# pc_healthypi_5_3.net
KiCad netlist of a schematic drawn in EAGLE
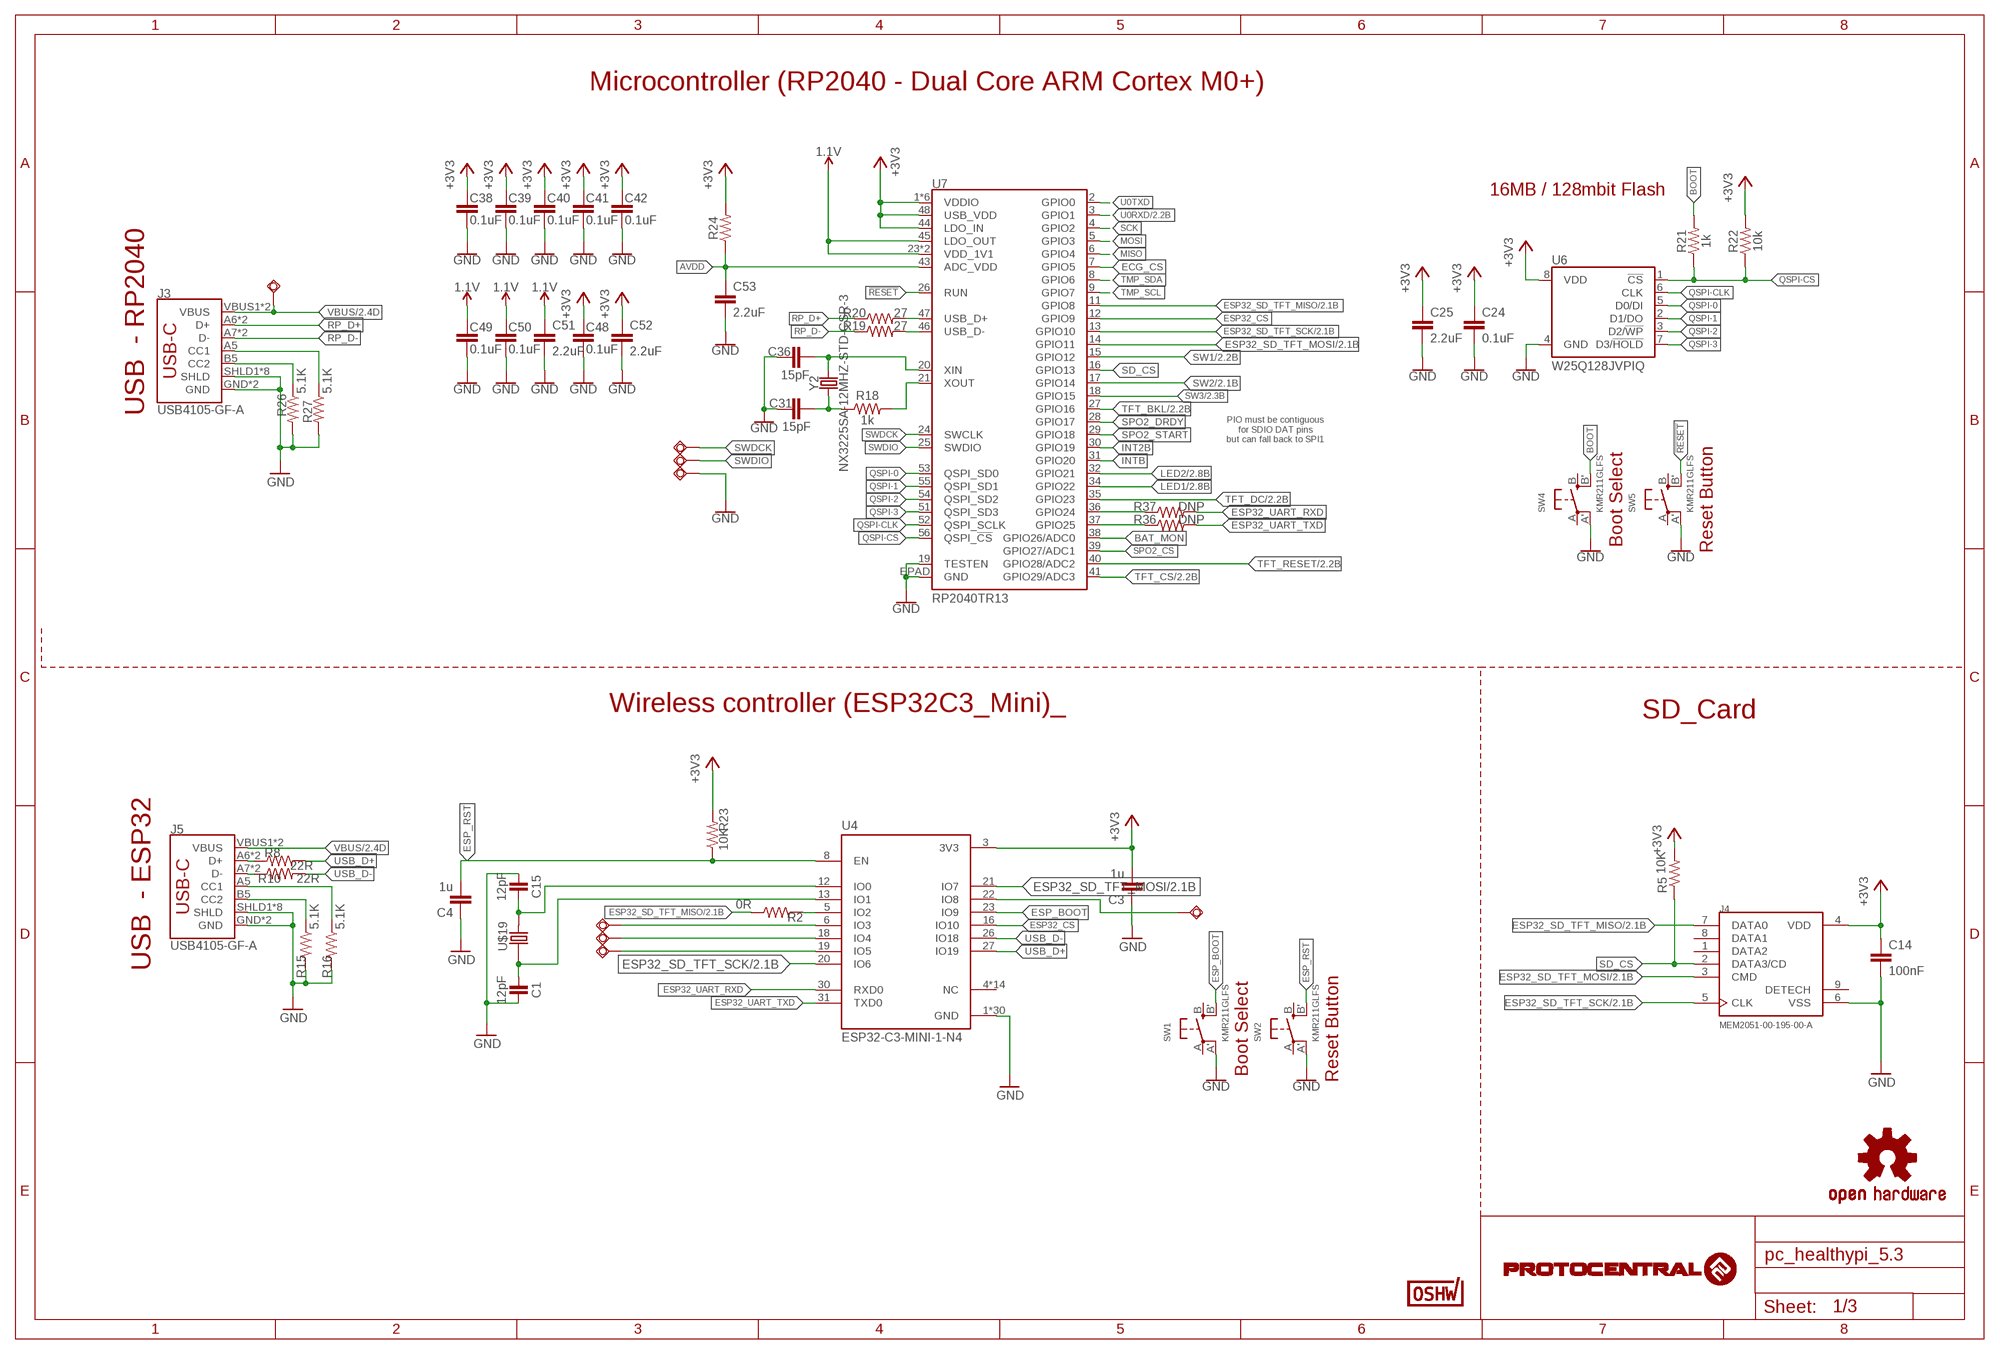
[diagram p0: schematic, sheet 1]
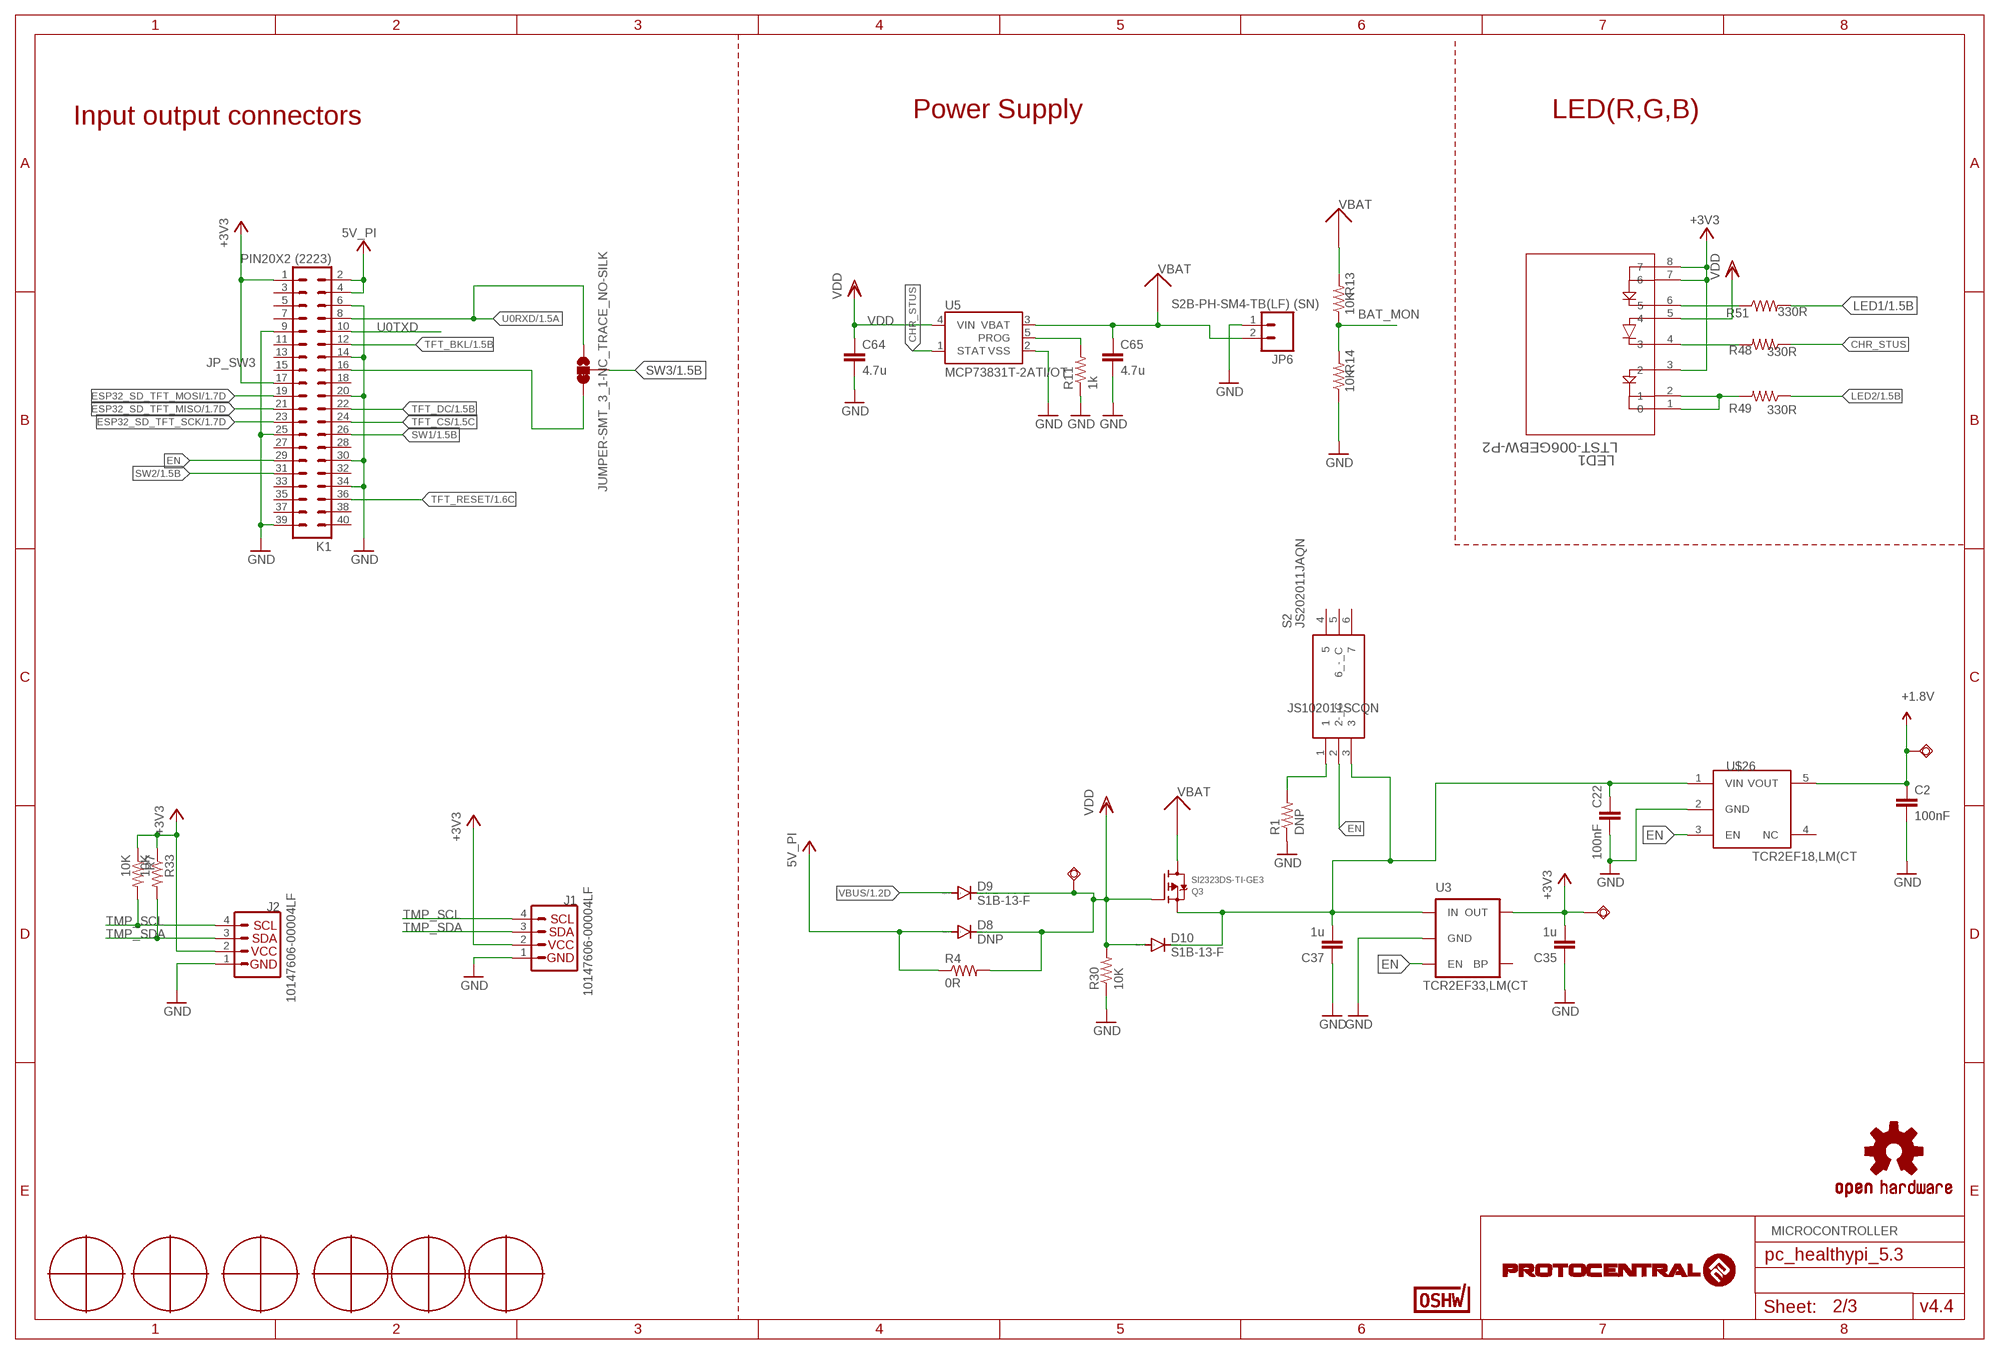
[diagram p1: schematic, sheet 2]
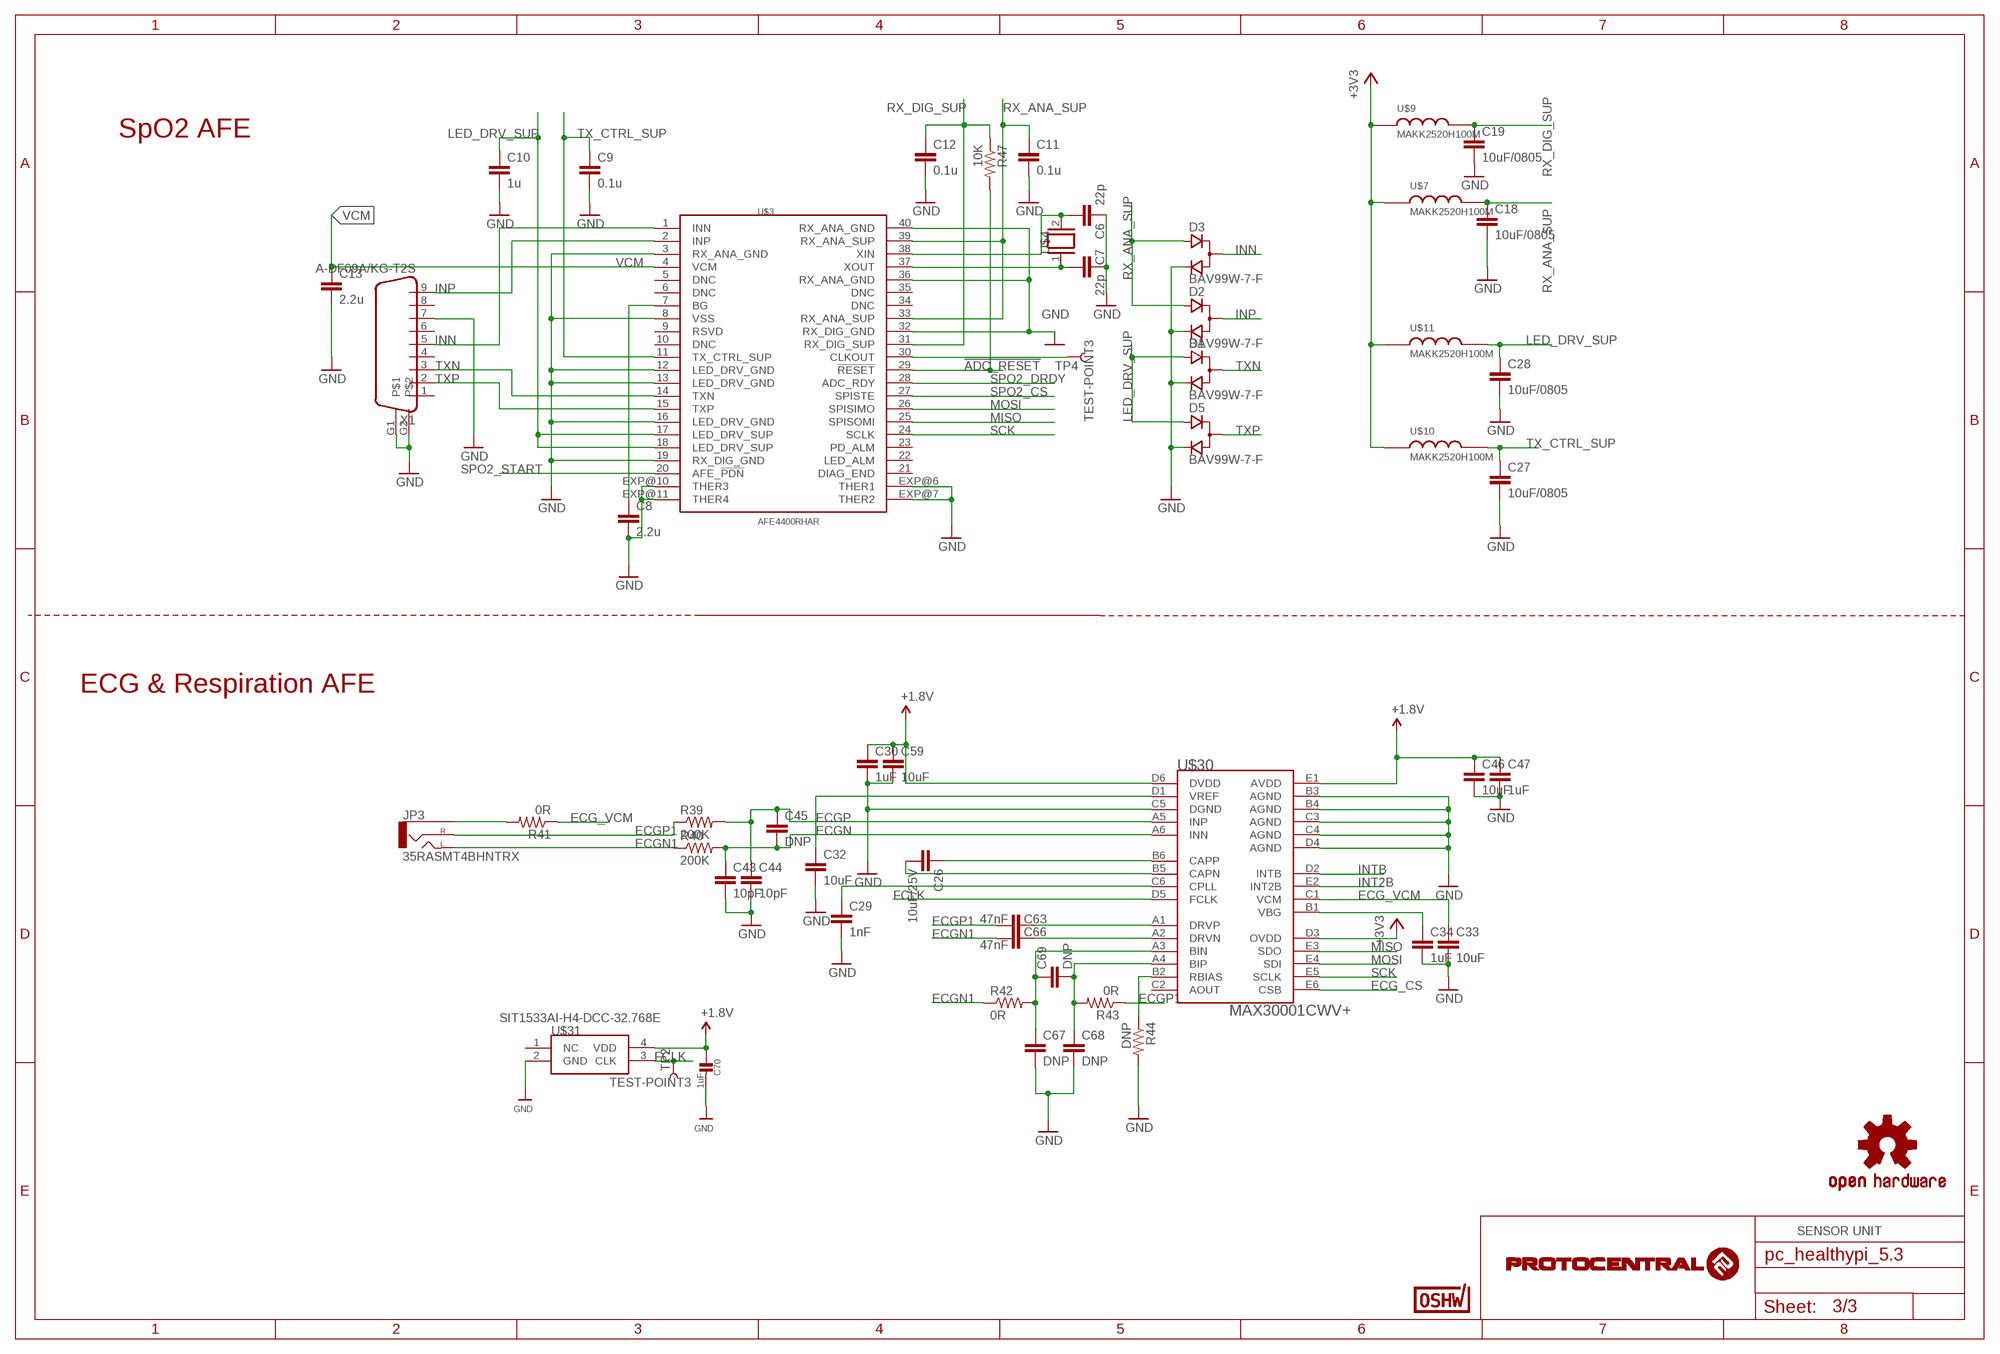
[diagram p2: schematic, sheet 3]

(export (version "E")
  (design (tool "Eeschema 10.0.6"))
  (components
    (comp (ref "C1")
      (value "12pF")
      (footprint "eagle-import:C0402")
      (libsource (lib "eagle-import") (part "CAPACITORS-0402"))
    )
    (comp (ref "C3")
      (value "1u")
      (footprint "eagle-import:C0402")
      (libsource (lib "eagle-import") (part "rcl_334_C-EUC0402"))
    )
    (comp (ref "C4")
      (value "1u")
      (footprint "eagle-import:C0402")
      (libsource (lib "eagle-import") (part "rcl_334_C-EUC0402"))
    )
    (comp (ref "C14")
      (value "100nF")
      (footprint "eagle-import:C0402")
      (libsource (lib "eagle-import") (part "C-EUC0402"))
    )
    (comp (ref "C15")
      (value "12pF")
      (footprint "eagle-import:C0402")
      (libsource (lib "eagle-import") (part "CAPACITORS-0402"))
    )
    (comp (ref "C24")
      (value "0.1uF")
      (footprint "eagle-import:0402-TIGHT")
      (libsource (lib "eagle-import") (part "0.1UF-0402T-6.3V-10%-X7R"))
    )
    (comp (ref "C25")
      (value "2.2uF")
      (footprint "eagle-import:0402-TIGHT")
      (libsource (lib "eagle-import") (part "2.2UF-0402_TIGHT-10V-10%-X5R"))
    )
    (comp (ref "C31")
      (value "15pF")
      (footprint "eagle-import:0402-TIGHT")
      (libsource (lib "eagle-import") (part "15PF-0402T-50V-5%"))
    )
    (comp (ref "C36")
      (value "15pF")
      (footprint "eagle-import:0402-TIGHT")
      (libsource (lib "eagle-import") (part "15PF-0402T-50V-5%"))
    )
    (comp (ref "C38")
      (value "0.1uF")
      (footprint "eagle-import:0402-TIGHT")
      (libsource (lib "eagle-import") (part "0.1UF-0402T-6.3V-10%-X7R"))
    )
    (comp (ref "C39")
      (value "0.1uF")
      (footprint "eagle-import:0402-TIGHT")
      (libsource (lib "eagle-import") (part "0.1UF-0402T-6.3V-10%-X7R"))
    )
    (comp (ref "C40")
      (value "0.1uF")
      (footprint "eagle-import:0402-TIGHT")
      (libsource (lib "eagle-import") (part "0.1UF-0402T-6.3V-10%-X7R"))
    )
    (comp (ref "C41")
      (value "0.1uF")
      (footprint "eagle-import:0402-TIGHT")
      (libsource (lib "eagle-import") (part "0.1UF-0402T-6.3V-10%-X7R"))
    )
    (comp (ref "C42")
      (value "0.1uF")
      (footprint "eagle-import:0402-TIGHT")
      (libsource (lib "eagle-import") (part "0.1UF-0402T-6.3V-10%-X7R"))
    )
    (comp (ref "C48")
      (value "0.1uF")
      (footprint "eagle-import:0402-TIGHT")
      (libsource (lib "eagle-import") (part "0.1UF-0402T-6.3V-10%-X7R"))
    )
    (comp (ref "C49")
      (value "0.1uF")
      (footprint "eagle-import:0402-TIGHT")
      (libsource (lib "eagle-import") (part "0.1UF-0402T-6.3V-10%-X7R"))
    )
    (comp (ref "C50")
      (value "0.1uF")
      (footprint "eagle-import:0402-TIGHT")
      (libsource (lib "eagle-import") (part "0.1UF-0402T-6.3V-10%-X7R"))
    )
    (comp (ref "C51")
      (value "2.2uF")
      (footprint "eagle-import:0402-TIGHT")
      (libsource (lib "eagle-import") (part "2.2UF-0402_TIGHT-10V-10%-X5R"))
    )
    (comp (ref "C52")
      (value "2.2uF")
      (footprint "eagle-import:0402-TIGHT")
      (libsource (lib "eagle-import") (part "2.2UF-0402_TIGHT-10V-10%-X5R"))
    )
    (comp (ref "C53")
      (value "2.2uF")
      (footprint "eagle-import:0402-TIGHT")
      (libsource (lib "eagle-import") (part "2.2UF-0402_TIGHT-10V-10%-X5R"))
    )
    (comp (ref "J3")
      (value "USB4105-GF-A")
      (footprint "eagle-import:USB-C-16P")
      (libsource (lib "eagle-import") (part "USB_C16PIN"))
    )
    (comp (ref "J4")
      (value "MEM2051-00-195-00-A")
      (footprint "eagle-import:GCT_MEM2051-00-195-00-A")
      (fields (field (name "MF") "Global Connector Technology"))
      (libsource (lib "eagle-import") (part "MEM2051-00-195-00-A"))
    )
    (comp (ref "J5")
      (value "USB4105-GF-A")
      (footprint "eagle-import:USB-C-16P")
      (libsource (lib "eagle-import") (part "circuitects_38825256_USB_C16PIN"))
    )
    (comp (ref "R2")
      (value "0R")
      (footprint "eagle-import:R0402")
      (libsource (lib "eagle-import") (part "rcl_334_R-US_R0402"))
    )
    (comp (ref "R5")
      (value "10K")
      (footprint "eagle-import:R0402")
      (libsource (lib "eagle-import") (part "R-US_R0402"))
    )
    (comp (ref "R8")
      (value "22R")
      (footprint "eagle-import:R0402")
      (libsource (lib "eagle-import") (part "rcl_334_R-US_R0402"))
    )
    (comp (ref "R10")
      (value "22R")
      (footprint "eagle-import:R0402")
      (libsource (lib "eagle-import") (part "rcl_334_R-US_R0402"))
    )
    (comp (ref "R15")
      (value "5.1K")
      (footprint "eagle-import:R0402")
      (libsource (lib "eagle-import") (part "rcl_334_R-US_R0402"))
    )
    (comp (ref "R16")
      (value "5.1K")
      (footprint "eagle-import:R0402")
      (libsource (lib "eagle-import") (part "rcl_334_R-US_R0402"))
    )
    (comp (ref "R18")
      (value "1k")
      (footprint "eagle-import:0402-TIGHT")
      (libsource (lib "eagle-import") (part "1KOHM-0402T-1/16W-1%"))
    )
    (comp (ref "R19")
      (value "27")
      (footprint "eagle-import:0402-TIGHT")
      (libsource (lib "eagle-import") (part "27OHM"))
    )
    (comp (ref "R20")
      (value "27")
      (footprint "eagle-import:0402-TIGHT")
      (libsource (lib "eagle-import") (part "27OHM"))
    )
    (comp (ref "R21")
      (value "1k")
      (footprint "eagle-import:0402-TIGHT")
      (libsource (lib "eagle-import") (part "1KOHM-0402T-1/16W-1%"))
    )
    (comp (ref "R22")
      (value "10k")
      (footprint "eagle-import:0402-TIGHT")
      (libsource (lib "eagle-import") (part "10KOHM-0402T-1/16W-1%"))
    )
    (comp (ref "R23")
      (value "10K")
      (footprint "eagle-import:R0402")
      (libsource (lib "eagle-import") (part "rcl_334_R-US_R0402"))
    )
    (comp (ref "R24")
      (value "200OHM-0402T-1/16W-1%")
      (footprint "eagle-import:0402-TIGHT")
      (libsource (lib "eagle-import") (part "200OHM-0402T-1/16W-1%"))
    )
    (comp (ref "R26")
      (value "5.1K")
      (footprint "eagle-import:R0402")
      (libsource (lib "eagle-import") (part "rcl_334_R-US_R0402"))
    )
    (comp (ref "R27")
      (value "5.1K")
      (footprint "eagle-import:R0402")
      (libsource (lib "eagle-import") (part "rcl_334_R-US_R0402"))
    )
    (comp (ref "R36")
      (value "DNP")
      (footprint "eagle-import:0402-TIGHT")
      (libsource (lib "eagle-import") (part "27OHM"))
    )
    (comp (ref "R37")
      (value "DNP")
      (footprint "eagle-import:0402-TIGHT")
      (libsource (lib "eagle-import") (part "27OHM"))
    )
    (comp (ref "SW1")
      (value "KMR211GLFS")
      (footprint "eagle-import:BTN_KMR2_4.6X2.8")
      (libsource (lib "eagle-import") (part "SWITCH_TACT_SMT4.6X2.8"))
    )
    (comp (ref "SW2")
      (value "KMR211GLFS")
      (footprint "eagle-import:BTN_KMR2_4.6X2.8")
      (libsource (lib "eagle-import") (part "SWITCH_TACT_SMT4.6X2.8"))
    )
    (comp (ref "SW4")
      (value "KMR211GLFS")
      (footprint "eagle-import:BTN_KMR2_4.6X2.8")
      (libsource (lib "eagle-import") (part "SWITCH_TACT_SMT4.6X2.8"))
    )
    (comp (ref "SW5")
      (value "KMR211GLFS")
      (footprint "eagle-import:BTN_KMR2_4.6X2.8")
      (libsource (lib "eagle-import") (part "SWITCH_TACT_SMT4.6X2.8"))
    )
    (comp (ref "SWIO2")
      (value "TPSQTP11R")
      (footprint "eagle-import:TP11R")
      (libsource (lib "eagle-import") (part "TPSQTP11R"))
    )
    (comp (ref "SWIO3")
      (value "TPSQTP11R")
      (footprint "eagle-import:TP11R")
      (libsource (lib "eagle-import") (part "TPSQTP11R"))
    )
    (comp (ref "SWIO4")
      (value "TPSQTP11R")
      (footprint "eagle-import:TP11R")
      (libsource (lib "eagle-import") (part "TPSQTP11R"))
    )
    (comp (ref "SWIO6")
      (value "TPSQTP11R")
      (footprint "eagle-import:TP11R")
      (libsource (lib "eagle-import") (part "TPSQTP11R"))
    )
    (comp (ref "TP1")
      (value "TPSQTP11R")
      (footprint "eagle-import:TP11R")
      (libsource (lib "eagle-import") (part "TPSQTP11R"))
    )
    (comp (ref "TP5")
      (value "TPSQTP11R")
      (footprint "eagle-import:TP11R")
      (libsource (lib "eagle-import") (part "TPSQTP11R"))
    )
    (comp (ref "TP6")
      (value "TPSQTP11R")
      (footprint "eagle-import:TP11R")
      (libsource (lib "eagle-import") (part "TPSQTP11R"))
    )
    (comp (ref "TP7")
      (value "TPSQTP11R")
      (footprint "eagle-import:TP11R")
      (libsource (lib "eagle-import") (part "TPSQTP11R"))
    )
    (comp (ref "U$19")
      (value "520-327-12.5-34B(32.768KHZ)")
      (footprint "eagle-import:ECX-31B")
      (libsource (lib "eagle-import") (part "ECS-X-34B"))
    )
    (comp (ref "U$35")
      (value "OSHW-LOGOM")
      (footprint "eagle-import:OSHW-LOGO-M")
      (libsource (lib "eagle-import") (part "OSHW-LOGOM"))
    )
    (comp (ref "U$37")
      (value "CERT-SMALL")
      (footprint "eagle-import:CERT-SMALL-SILK")
      (libsource (lib "eagle-import") (part "CERT-SMALL"))
    )
    (comp (ref "U4")
      (value "ESP32-C3-MINI-1-N4")
      (footprint "eagle-import:XCVR_ESP32-C3-MINI-1-N4")
      (fields (field (name "MF") "Espressif Systems"))
      (libsource (lib "eagle-import") (part "ESP32-C3-MINI-1-N4"))
    )
    (comp (ref "U6")
      (value "W25Q128JVPIQ")
      (footprint "eagle-import:WSON-8-6X5-SKINNY_CENTERPAD")
      (libsource (lib "eagle-import") (part "W25QXX128MBIT-6X5-SKINNY_CENTER"))
    )
    (comp (ref "U7")
      (value "RP2040TR13")
      (footprint "eagle-import:QFN-56")
      (libsource (lib "eagle-import") (part "RP2040"))
    )
    (comp (ref "Y2")
      (value "NX3225SA-12MHZ-STD-CSR-3")
      (footprint "eagle-import:CRYSTAL-SMD-2X2.5MM")
      (libsource (lib "eagle-import") (part "CRYSTAL-12MHZ"))
    )
    (comp (ref "C6")
      (value "22p")
      (footprint "eagle-import:C0402")
      (libsource (lib "eagle-import") (part "rcl_334_C-EUC0402"))
    )
    (comp (ref "C7")
      (value "22p")
      (footprint "eagle-import:C0402")
      (libsource (lib "eagle-import") (part "rcl_334_C-EUC0402"))
    )
    (comp (ref "C8")
      (value "2.2u")
      (footprint "eagle-import:C0402")
      (libsource (lib "eagle-import") (part "rcl_334_C-EUC0402"))
    )
    (comp (ref "C9")
      (value "0.1u")
      (footprint "eagle-import:C0402")
      (libsource (lib "eagle-import") (part "rcl_334_C-EUC0402"))
    )
    (comp (ref "C10")
      (value "1u")
      (footprint "eagle-import:C0805")
      (libsource (lib "eagle-import") (part "rcl_334_C-EUC0805"))
    )
    (comp (ref "C11")
      (value "0.1u")
      (footprint "eagle-import:C0402")
      (libsource (lib "eagle-import") (part "rcl_334_C-EUC0402"))
    )
    (comp (ref "C12")
      (value "0.1u")
      (footprint "eagle-import:C0402")
      (libsource (lib "eagle-import") (part "rcl_334_C-EUC0402"))
    )
    (comp (ref "C13")
      (value "2.2u")
      (footprint "eagle-import:C0402")
      (libsource (lib "eagle-import") (part "rcl_334_C-EUC0402"))
    )
    (comp (ref "C18")
      (value "10uF/0805")
      (footprint "eagle-import:C0805")
      (libsource (lib "eagle-import") (part "rcl_334_C-EUC0805"))
    )
    (comp (ref "C19")
      (value "10uF/0805")
      (footprint "eagle-import:C0805")
      (libsource (lib "eagle-import") (part "rcl_334_C-EUC0805"))
    )
    (comp (ref "C26")
      (value "10uF/25V")
      (footprint "eagle-import:C0805")
      (libsource (lib "eagle-import") (part "rcl_334_C-EUC0805"))
    )
    (comp (ref "C27")
      (value "10uF/0805")
      (footprint "eagle-import:C0805")
      (libsource (lib "eagle-import") (part "rcl_334_C-EUC0805"))
    )
    (comp (ref "C28")
      (value "10uF/0805")
      (footprint "eagle-import:C0805")
      (libsource (lib "eagle-import") (part "rcl_334_C-EUC0805"))
    )
    (comp (ref "C29")
      (value "1nF")
      (footprint "eagle-import:C0402")
      (libsource (lib "eagle-import") (part "rcl_334_C-EUC0402"))
    )
    (comp (ref "C30")
      (value "1uF")
      (footprint "eagle-import:C0402")
      (libsource (lib "eagle-import") (part "rcl_334_C-EUC0402"))
    )
    (comp (ref "C32")
      (value "10uF")
      (footprint "eagle-import:C0805")
      (libsource (lib "eagle-import") (part "rcl_334_C-EUC0805"))
    )
    (comp (ref "C33")
      (value "10uF")
      (footprint "eagle-import:C0805")
      (libsource (lib "eagle-import") (part "rcl_334_C-EUC0805"))
    )
    (comp (ref "C34")
      (value "1uF")
      (footprint "eagle-import:C0402")
      (libsource (lib "eagle-import") (part "rcl_334_C-EUC0402"))
    )
    (comp (ref "C43")
      (value "10pF")
      (footprint "eagle-import:C0402")
      (libsource (lib "eagle-import") (part "rcl_334_C-EUC0402"))
    )
    (comp (ref "C44")
      (value "10pF")
      (footprint "eagle-import:C0402")
      (libsource (lib "eagle-import") (part "rcl_334_C-EUC0402"))
    )
    (comp (ref "C45")
      (value "DNP")
      (footprint "eagle-import:C0402")
      (libsource (lib "eagle-import") (part "rcl_334_C-EUC0402"))
    )
    (comp (ref "C46")
      (value "10uF")
      (footprint "eagle-import:C0805")
      (libsource (lib "eagle-import") (part "rcl_334_C-EUC0805"))
    )
    (comp (ref "C47")
      (value "1uF")
      (footprint "eagle-import:C0402")
      (libsource (lib "eagle-import") (part "rcl_334_C-EUC0402"))
    )
    (comp (ref "C59")
      (value "10uF")
      (footprint "eagle-import:C0805")
      (libsource (lib "eagle-import") (part "rcl_334_C-EUC0805"))
    )
    (comp (ref "C63")
      (value "47nF")
      (footprint "eagle-import:C0402")
      (libsource (lib "eagle-import") (part "rcl_334_C-EUC0402"))
    )
    (comp (ref "C66")
      (value "47nF")
      (footprint "eagle-import:C0402")
      (libsource (lib "eagle-import") (part "rcl_334_C-EUC0402"))
    )
    (comp (ref "C67")
      (value "DNP")
      (footprint "eagle-import:C0402")
      (libsource (lib "eagle-import") (part "rcl_334_C-EUC0402"))
    )
    (comp (ref "C68")
      (value "DNP")
      (footprint "eagle-import:C0402")
      (libsource (lib "eagle-import") (part "rcl_334_C-EUC0402"))
    )
    (comp (ref "C69")
      (value "DNP")
      (footprint "eagle-import:C0402")
      (libsource (lib "eagle-import") (part "rcl_334_C-EUC0402"))
    )
    (comp (ref "C70")
      (value "1uF")
      (footprint "eagle-import:0402")
      (libsource (lib "eagle-import") (part "CAP_CERAMIC0402"))
    )
    (comp (ref "D1")
      (value "BAV99W-7-F")
      (footprint "eagle-import:SOT323")
      (libsource (lib "eagle-import") (part "D_ACACSOT323"))
    )
    (comp (ref "D2")
      (value "BAV99W-7-F")
      (footprint "eagle-import:SOT323")
      (libsource (lib "eagle-import") (part "D_ACACSOT323"))
    )
    (comp (ref "D3")
      (value "BAV99W-7-F")
      (footprint "eagle-import:SOT323")
      (libsource (lib "eagle-import") (part "D_ACACSOT323"))
    )
    (comp (ref "D5")
      (value "BAV99W-7-F")
      (footprint "eagle-import:SOT323")
      (libsource (lib "eagle-import") (part "D_ACACSOT323"))
    )
    (comp (ref "JP3")
      (value "35RASMT4BHNTRX")
      (footprint "eagle-import:AUDIO-JACK-3.5MM-SMD")
      (libsource (lib "eagle-import") (part "AUDIO-JACKSMD2"))
    )
    (comp (ref "R39")
      (value "200K")
      (footprint "eagle-import:0805")
      (libsource (lib "eagle-import") (part "RESISTOR0805-RES"))
    )
    (comp (ref "R40")
      (value "200K")
      (footprint "eagle-import:0805")
      (libsource (lib "eagle-import") (part "RESISTOR0805-RES"))
    )
    (comp (ref "R41")
      (value "0R")
      (footprint "eagle-import:0805")
      (libsource (lib "eagle-import") (part "RESISTOR0805-RES"))
    )
    (comp (ref "R42")
      (value "0R")
      (footprint "eagle-import:0402-RES")
      (libsource (lib "eagle-import") (part "RESISTOR0402-RES"))
    )
    (comp (ref "R43")
      (value "0R")
      (footprint "eagle-import:0402-RES")
      (libsource (lib "eagle-import") (part "RESISTOR0402-RES"))
    )
    (comp (ref "R44")
      (value "DNP")
      (footprint "eagle-import:0402-RES")
      (libsource (lib "eagle-import") (part "RESISTOR0402-RES"))
    )
    (comp (ref "R47")
      (value "10K")
      (footprint "eagle-import:R0402")
      (libsource (lib "eagle-import") (part "rcl_334_R-US_R0402"))
    )
    (comp (ref "TP2")
      (value "TEST-POINT3")
      (footprint "eagle-import:PAD.03X.03")
      (libsource (lib "eagle-import") (part "TEST-POINT3"))
    )
    (comp (ref "TP4")
      (value "TEST-POINT3")
      (footprint "eagle-import:PAD.03X.03")
      (libsource (lib "eagle-import") (part "TEST-POINT3"))
    )
    (comp (ref "U$3")
      (value "AFE4400RHAR")
      (footprint "eagle-import:QFN-40")
      (libsource (lib "eagle-import") (part "AFE4400"))
    )
    (comp (ref "U$4")
      (value "ABM3-8.000MHZ-B4Y-T")
      (footprint "eagle-import:XTAL_HC49P488W43L1150T466H350")
      (fields (field (name "MF") "Citizen Finedevice Co Ltd") (field (name "MP") "HC-49/U-S16000000ABJB"))
      (libsource (lib "eagle-import") (part "HC-49/U-S16000000ABJB"))
    )
    (comp (ref "U$7")
      (value "MAKK2520H100M")
      (footprint "eagle-import:LPS")
      (libsource (lib "eagle-import") (part "LPS"))
    )
    (comp (ref "U$9")
      (value "MAKK2520H100M")
      (footprint "eagle-import:LPS")
      (libsource (lib "eagle-import") (part "LPS"))
    )
    (comp (ref "U$10")
      (value "MAKK2520H100M")
      (footprint "eagle-import:LPS")
      (libsource (lib "eagle-import") (part "LPS"))
    )
    (comp (ref "U$11")
      (value "MAKK2520H100M")
      (footprint "eagle-import:LPS")
      (libsource (lib "eagle-import") (part "LPS"))
    )
    (comp (ref "U$24")
      (value "OSHW-LOGOM")
      (footprint "eagle-import:OSHW-LOGO-M")
      (libsource (lib "eagle-import") (part "OSHW-LOGOM"))
    )
    (comp (ref "U$30")
      (value "MAX30001CWV+")
      (footprint "eagle-import:30WLP")
      (libsource (lib "eagle-import") (part "MAX30001CWV+"))
    )
    (comp (ref "U$31")
      (value "SIT1533AI-H4-DCC-32.768E")
      (footprint "eagle-import:SIT1533")
      (libsource (lib "eagle-import") (part "SIT1533"))
    )
    (comp (ref "U$36")
      (value "CERT-SMALL")
      (footprint "eagle-import:CERT-SMALL-SILK")
      (libsource (lib "eagle-import") (part "CERT-SMALL"))
    )
    (comp (ref "X1")
      (value "A-DF09A/KG-T2S")
      (footprint "eagle-import:DB9")
      (libsource (lib "eagle-import") (part "DB9"))
    )
    (comp (ref "C2")
      (value "100nF")
      (footprint "eagle-import:C0402")
      (libsource (lib "eagle-import") (part "rcl_334_C-EUC0402"))
    )
    (comp (ref "C22")
      (value "100nF")
      (footprint "eagle-import:C0402")
      (libsource (lib "eagle-import") (part "rcl_334_C-EUC0402"))
    )
    (comp (ref "C35")
      (value "1u")
      (footprint "eagle-import:C0402")
      (libsource (lib "eagle-import") (part "rcl_334_C-EUC0402"))
    )
    (comp (ref "C37")
      (value "1u")
      (footprint "eagle-import:C0402")
      (libsource (lib "eagle-import") (part "rcl_334_C-EUC0402"))
    )
    (comp (ref "C64")
      (value "4.7u")
      (footprint "eagle-import:C0805")
      (libsource (lib "eagle-import") (part "rcl_334_C-EUC0805"))
    )
    (comp (ref "C65")
      (value "4.7u")
      (footprint "eagle-import:C0805")
      (libsource (lib "eagle-import") (part "rcl_334_C-EUC0805"))
    )
    (comp (ref "D8")
      (value "DNP")
      (footprint "eagle-import:SOD-123_MINI-SMA")
      (libsource (lib "eagle-import") (part "CGRM400-G1"))
    )
    (comp (ref "D9")
      (value "S1B-13-F")
      (footprint "eagle-import:SOD-123_MINI-SMA")
      (libsource (lib "eagle-import") (part "CGRM400-G1"))
    )
    (comp (ref "D10")
      (value "S1B-13-F")
      (footprint "eagle-import:SOD-123_MINI-SMA")
      (libsource (lib "eagle-import") (part "CGRM400-G1"))
    )
    (comp (ref "J1")
      (value "10147606-00004LF")
      (footprint "eagle-import:JST04_1MM_RA")
      (libsource (lib "eagle-import") (part "QWIIC_CONNECTORJS-1MM"))
    )
    (comp (ref "J2")
      (value "10147606-00004LF")
      (footprint "eagle-import:JST04_1MM_RA")
      (libsource (lib "eagle-import") (part "QWIIC_CONNECTORJS-1MM"))
    )
    (comp (ref "JP6")
      (value "S2B-PH-SM4-TB(LF) (SN)")
      (footprint "eagle-import:JST-2-SMD")
      (libsource (lib "eagle-import") (part "M02-JST-2MM-SMT"))
    )
    (comp (ref "JP_SW3")
      (value "JUMPER-SMT_3_1-NC_TRACE_NO-SILK")
      (footprint "eagle-import:SMT-JUMPER_3_1-NC_TRACE_NO-SILK")
      (libsource (lib "eagle-import") (part "JUMPER-SMT_3_1-NC_TRACE_NO-SILK"))
    )
    (comp (ref "K1")
      (value "PIN20X2 (2223)")
      (footprint "eagle-import:PIN_20X2")
      (libsource (lib "eagle-import") (part "PIN20X2"))
    )
    (comp (ref "LED1")
      (value "LTST-006GEBW-P2")
      (footprint "eagle-import:LTST-008BGEW_LTO")
      (fields (field (name "COPYRIGHT") "Copyright (C) 2023 Ultra Librarian. All rights reserved."))
      (libsource (lib "eagle-import") (part "LTST-006GEBW-P2"))
    )
    (comp (ref "Q3")
      (value "SI2323DS-TI-GE3")
      (footprint "eagle-import:SOT23-R")
      (libsource (lib "eagle-import") (part "MOSFET-P"))
    )
    (comp (ref "R1")
      (value "DNP")
      (footprint "eagle-import:R0402")
      (libsource (lib "eagle-import") (part "rcl_334_R-US_R0402"))
    )
    (comp (ref "R4")
      (value "0R")
      (footprint "eagle-import:0805")
      (libsource (lib "eagle-import") (part "RESISTOR0805-RES"))
    )
    (comp (ref "R7")
      (value "10K")
      (footprint "eagle-import:R0402")
      (libsource (lib "eagle-import") (part "rcl_334_R-US_R0402"))
    )
    (comp (ref "R11")
      (value "1k")
      (footprint "eagle-import:R0402")
      (libsource (lib "eagle-import") (part "rcl_334_R-US_R0402"))
    )
    (comp (ref "R13")
      (value "10K")
      (footprint "eagle-import:R0402")
      (libsource (lib "eagle-import") (part "rcl_334_R-US_R0402"))
    )
    (comp (ref "R14")
      (value "10K")
      (footprint "eagle-import:R0402")
      (libsource (lib "eagle-import") (part "rcl_334_R-US_R0402"))
    )
    (comp (ref "R30")
      (value "10K")
      (footprint "eagle-import:R0402")
      (libsource (lib "eagle-import") (part "rcl_334_R-US_R0402"))
    )
    (comp (ref "R33")
      (value "10K")
      (footprint "eagle-import:R0402")
      (libsource (lib "eagle-import") (part "rcl_334_R-US_R0402"))
    )
    (comp (ref "R48")
      (value "330R")
      (footprint "eagle-import:0402-RES")
      (libsource (lib "eagle-import") (part "RESISTOR0402-RES"))
    )
    (comp (ref "R49")
      (value "330R")
      (footprint "eagle-import:0402-RES")
      (libsource (lib "eagle-import") (part "RESISTOR0402-RES"))
    )
    (comp (ref "R51")
      (value "330R")
      (footprint "eagle-import:0402-RES")
      (libsource (lib "eagle-import") (part "RESISTOR0402-RES"))
    )
    (comp (ref "S2")
      (value "JS202011JAQN")
      (footprint "eagle-import:JS202011JAQN")
      (fields (field (name "MF") "C&K"))
      (libsource (lib "eagle-import") (part "JS202011JAQN"))
    )
    (comp (ref "SWIO1")
      (value "TPSQTP11R")
      (footprint "eagle-import:TP11R")
      (libsource (lib "eagle-import") (part "TPSQTP11R"))
    )
    (comp (ref "SWIO5")
      (value "TPSQTP11R")
      (footprint "eagle-import:TP11R")
      (libsource (lib "eagle-import") (part "TPSQTP11R"))
    )
    (comp (ref "SWIO7")
      (value "TPSQTP11R")
      (footprint "eagle-import:TP11R")
      (libsource (lib "eagle-import") (part "TPSQTP11R"))
    )
    (comp (ref "U$1")
      (value "FUDCIALPOINTS")
      (footprint "eagle-import:FIDUCIALPOINTS")
      (libsource (lib "eagle-import") (part "circuitects_38825256_FUDCIALPOINTS"))
    )
    (comp (ref "U$5")
      (value "OSHW-LOGOM")
      (footprint "eagle-import:OSHW-LOGO-M")
      (libsource (lib "eagle-import") (part "OSHW-LOGOM"))
    )
    (comp (ref "U$13")
      (value "CERT-SMALL")
      (footprint "eagle-import:CERT-SMALL-SILK")
      (libsource (lib "eagle-import") (part "CERT-SMALL"))
    )
    (comp (ref "U$21")
      (value "FUDCIALPOINTS")
      (footprint "eagle-import:FIDUCIALPOINTS")
      (libsource (lib "eagle-import") (part "FUDCIALPOINTS"))
    )
    (comp (ref "U$23")
      (value "FUDCIALPOINTS")
      (footprint "eagle-import:FIDUCIALPOINTS")
      (libsource (lib "eagle-import") (part "circuitects_38825256_FUDCIALPOINTS"))
    )
    (comp (ref "U$25")
      (value "FUDCIALPOINTS")
      (footprint "eagle-import:FIDUCIALPOINTS")
      (libsource (lib "eagle-import") (part "circuitects_38825256_FUDCIALPOINTS"))
    )
    (comp (ref "U$26")
      (value "TCR2EF18,LM(CT")
      (footprint "eagle-import:SOT95P285X140-5N")
      (libsource (lib "eagle-import") (part "AP7354D-18W5-7"))
    )
    (comp (ref "U$28")
      (value "FUDCIALPOINTS")
      (footprint "eagle-import:FIDUCIALPOINTS")
      (libsource (lib "eagle-import") (part "FUDCIALPOINTS"))
    )
    (comp (ref "U$29")
      (value "FUDCIALPOINTS")
      (footprint "eagle-import:FIDUCIALPOINTS")
      (libsource (lib "eagle-import") (part "FUDCIALPOINTS"))
    )
    (comp (ref "U3")
      (value "TCR2EF33,LM(CT")
      (footprint "eagle-import:SOT23-5")
      (libsource (lib "eagle-import") (part "V_REG_LDOSMD"))
    )
    (comp (ref "U5")
      (value "MCP73831T-2ATI/OT")
      (footprint "eagle-import:SOT23-5")
      (libsource (lib "eagle-import") (part "MCP73831"))
    )
  )
  (nets
    (net (code "1") (name "+1.8V") (class "Default")
      (node (ref "C2") (pin "1") (pinfunction "1_1") (pintype "passive"))
      (node (ref "C30") (pin "1") (pinfunction "1_1") (pintype "passive"))
      (node (ref "C46") (pin "1") (pinfunction "1_1") (pintype "passive"))
      (node (ref "C47") (pin "1") (pinfunction "1_1") (pintype "passive"))
      (node (ref "C59") (pin "1") (pinfunction "1_1") (pintype "passive"))
      (node (ref "C70") (pin "1") (pinfunction "P$1_1") (pintype "passive"))
      (node (ref "SWIO5") (pin "TP") (pinfunction "TP_TP") (pintype "input"))
      (node (ref "U$26") (pin "5") (pinfunction "VOUT_5") (pintype "bidirectional"))
      (node (ref "U$30") (pin "D6") (pinfunction "DVDD_D6") (pintype "bidirectional"))
      (node (ref "U$30") (pin "E1") (pinfunction "AVDD_E1") (pintype "bidirectional"))
      (node (ref "U$31") (pin "4") (pinfunction "VDD_4") (pintype "bidirectional"))
    )
    (net (code "2") (name "+3V3") (class "Default")
      (node (ref "C14") (pin "1") (pinfunction "1_1") (pintype "passive"))
      (node (ref "C24") (pin "1") (pinfunction "1_1") (pintype "passive"))
      (node (ref "C25") (pin "1") (pinfunction "1_1") (pintype "passive"))
      (node (ref "C3") (pin "2") (pinfunction "2_2") (pintype "passive"))
      (node (ref "C35") (pin "2") (pinfunction "2_2") (pintype "passive"))
      (node (ref "C38") (pin "1") (pinfunction "1_1") (pintype "passive"))
      (node (ref "C39") (pin "1") (pinfunction "1_1") (pintype "passive"))
      (node (ref "C40") (pin "1") (pinfunction "1_1") (pintype "passive"))
      (node (ref "C41") (pin "1") (pinfunction "1_1") (pintype "passive"))
      (node (ref "C42") (pin "1") (pinfunction "1_1") (pintype "passive"))
      (node (ref "C48") (pin "1") (pinfunction "1_1") (pintype "passive"))
      (node (ref "C52") (pin "1") (pinfunction "1_1") (pintype "passive"))
      (node (ref "J1") (pin "2") (pinfunction "2_2") (pintype "power_in"))
      (node (ref "J2") (pin "2") (pinfunction "2_2") (pintype "power_in"))
      (node (ref "J4") (pin "4") (pinfunction "VDD_4") (pintype "power_in"))
      (node (ref "K1") (pin "1") (pinfunction "1_1") (pintype "passive"))
      (node (ref "K1") (pin "17") (pinfunction "17_17") (pintype "passive"))
      (node (ref "LED1") (pin "3") (pinfunction "2_3") (pintype "passive"))
      (node (ref "LED1") (pin "7") (pinfunction "6_7") (pintype "passive"))
      (node (ref "LED1") (pin "8") (pinfunction "7_8") (pintype "passive"))
      (node (ref "R22") (pin "2") (pinfunction "2_2") (pintype "passive"))
      (node (ref "R23") (pin "2") (pinfunction "2_2") (pintype "passive"))
      (node (ref "R24") (pin "2") (pinfunction "2_2") (pintype "passive"))
      (node (ref "R33") (pin "1") (pinfunction "1_1") (pintype "passive"))
      (node (ref "R5") (pin "2") (pinfunction "2_2") (pintype "passive"))
      (node (ref "R7") (pin "1") (pinfunction "1_1") (pintype "passive"))
      (node (ref "SWIO1") (pin "TP") (pinfunction "TP_TP") (pintype "input"))
      (node (ref "U$10") (pin "1") (pinfunction "P$1_1") (pintype "bidirectional"))
      (node (ref "U$11") (pin "1") (pinfunction "P$1_1") (pintype "bidirectional"))
      (node (ref "U$30") (pin "D3") (pinfunction "OVDD_D3") (pintype "bidirectional"))
      (node (ref "U$7") (pin "1") (pinfunction "P$1_1") (pintype "bidirectional"))
      (node (ref "U$9") (pin "1") (pinfunction "P$1_1") (pintype "bidirectional"))
      (node (ref "U3") (pin "5") (pinfunction "OUT_5") (pintype "passive"))
      (node (ref "U4") (pin "3") (pinfunction "3V3_3") (pintype "power_in"))
      (node (ref "U6") (pin "8") (pinfunction "VDD_8") (pintype "bidirectional"))
      (node (ref "U7") (pin "1") (pinfunction "VDDIO_1") (pintype "bidirectional"))
      (node (ref "U7") (pin "10") (pinfunction "VDDIO_10") (pintype "bidirectional"))
      (node (ref "U7") (pin "22") (pinfunction "VDDIO_22") (pintype "bidirectional"))
      (node (ref "U7") (pin "33") (pinfunction "VDDIO_33") (pintype "bidirectional"))
      (node (ref "U7") (pin "42") (pinfunction "VDDIO_42") (pintype "bidirectional"))
      (node (ref "U7") (pin "44") (pinfunction "LDO_IN_44") (pintype "bidirectional"))
      (node (ref "U7") (pin "48") (pinfunction "USB_VDD_48") (pintype "bidirectional"))
      (node (ref "U7") (pin "49") (pinfunction "VDDIO_49") (pintype "bidirectional"))
    )
    (net (code "3") (name "+5V") (class "Default")
      (node (ref "D8") (pin "A") (pinfunction "A_A") (pintype "passive"))
      (node (ref "K1") (pin "2") (pinfunction "2_2") (pintype "passive"))
      (node (ref "K1") (pin "4") (pinfunction "4_4") (pintype "passive"))
      (node (ref "R4") (pin "1") (pinfunction "1_1") (pintype "passive"))
    )
    (net (code "4") (name "1.1V") (class "Default")
      (node (ref "C49") (pin "1") (pinfunction "1_1") (pintype "passive"))
      (node (ref "C50") (pin "1") (pinfunction "1_1") (pintype "passive"))
      (node (ref "C51") (pin "1") (pinfunction "1_1") (pintype "passive"))
      (node (ref "U7") (pin "23") (pinfunction "VDD_1V1_23") (pintype "bidirectional"))
      (node (ref "U7") (pin "45") (pinfunction "LDO_OUT_45") (pintype "bidirectional"))
      (node (ref "U7") (pin "50") (pinfunction "VDD_1V1_50") (pintype "bidirectional"))
    )
    (net (code "5") (name "AVDD") (class "Default")
      (node (ref "C53") (pin "1") (pinfunction "1_1") (pintype "passive"))
      (node (ref "R24") (pin "1") (pinfunction "1_1") (pintype "passive"))
      (node (ref "U7") (pin "43") (pinfunction "ADC_VDD_43") (pintype "bidirectional"))
    )
    (net (code "6") (name "BAT_MON") (class "Default")
      (node (ref "R13") (pin "1") (pinfunction "1_1") (pintype "passive"))
      (node (ref "R14") (pin "2") (pinfunction "2_2") (pintype "passive"))
      (node (ref "U7") (pin "38") (pinfunction "GPIO26/ADC0_38") (pintype "bidirectional"))
    )
    (net (code "7") (name "BOOT") (class "Default")
      (node (ref "R21") (pin "2") (pinfunction "2_2") (pintype "passive"))
      (node (ref "SW4") (pin "B'") (pinfunction "S1_B'") (pintype "passive"))
    )
    (net (code "8") (name "CHR_STUS") (class "Default")
      (node (ref "R48") (pin "1") (pinfunction "1_1") (pintype "passive"))
      (node (ref "U5") (pin "1") (pinfunction "STAT_1") (pintype "output"))
    )
    (net (code "9") (name "ECGN") (class "Default")
      (node (ref "C43") (pin "1") (pinfunction "1_1") (pintype "passive"))
      (node (ref "C45") (pin "2") (pinfunction "2_2") (pintype "passive"))
      (node (ref "R40") (pin "2") (pinfunction "2_2") (pintype "passive"))
      (node (ref "U$30") (pin "A6") (pinfunction "INN_A6") (pintype "bidirectional"))
    )
    (net (code "10") (name "ECGN1") (class "Default")
      (node (ref "C66") (pin "1") (pinfunction "1_1") (pintype "passive"))
      (node (ref "JP3") (pin "TIP") (pinfunction "LEFT_TIP") (pintype "bidirectional"))
      (node (ref "R40") (pin "1") (pinfunction "1_1") (pintype "passive"))
      (node (ref "R42") (pin "1") (pinfunction "1_1") (pintype "passive"))
    )
    (net (code "11") (name "ECGP") (class "Default")
      (node (ref "C44") (pin "1") (pinfunction "1_1") (pintype "passive"))
      (node (ref "C45") (pin "1") (pinfunction "1_1") (pintype "passive"))
      (node (ref "R39") (pin "2") (pinfunction "2_2") (pintype "passive"))
      (node (ref "U$30") (pin "A5") (pinfunction "INP_A5") (pintype "bidirectional"))
    )
    (net (code "12") (name "ECGP1") (class "Default")
      (node (ref "C63") (pin "1") (pinfunction "1_1") (pintype "passive"))
      (node (ref "JP3") (pin "RING") (pinfunction "RIGHT_RING") (pintype "bidirectional"))
      (node (ref "R39") (pin "1") (pinfunction "1_1") (pintype "passive"))
      (node (ref "R43") (pin "1") (pinfunction "1_1") (pintype "passive"))
    )
    (net (code "13") (name "ECG_CS") (class "Default")
      (node (ref "U$30") (pin "E6") (pinfunction "CSB_E6") (pintype "bidirectional"))
      (node (ref "U7") (pin "7") (pinfunction "GPIO5_7") (pintype "bidirectional"))
    )
    (net (code "14") (name "ECG_VCM") (class "Default")
      (node (ref "C33") (pin "1") (pinfunction "1_1") (pintype "passive"))
      (node (ref "R41") (pin "1") (pinfunction "1_1") (pintype "passive"))
      (node (ref "U$30") (pin "C1") (pinfunction "VCM_C1") (pintype "bidirectional"))
    )
    (net (code "15") (name "EN") (class "Default")
      (node (ref "K1") (pin "29") (pinfunction "29_29") (pintype "passive"))
      (node (ref "S2") (pin "2") (pinfunction "2-_C_2") (pintype "bidirectional"))
      (node (ref "U$26") (pin "3") (pinfunction "EN_3") (pintype "bidirectional"))
      (node (ref "U3") (pin "3") (pinfunction "EN_3") (pintype "input"))
    )
    (net (code "16") (name "ESP32_CS") (class "Default")
      (node (ref "U4") (pin "16") (pinfunction "IO10_16") (pintype "bidirectional"))
      (node (ref "U7") (pin "12") (pinfunction "GPIO9_12") (pintype "bidirectional"))
    )
    (net (code "17") (name "ESP32_SD_TFT_MISO") (class "Default")
      (node (ref "J4") (pin "7") (pinfunction "DATA0_7") (pintype "bidirectional"))
      (node (ref "K1") (pin "21") (pinfunction "21_21") (pintype "passive"))
      (node (ref "R2") (pin "1") (pinfunction "1_1") (pintype "passive"))
      (node (ref "U7") (pin "11") (pinfunction "GPIO8_11") (pintype "bidirectional"))
    )
    (net (code "18") (name "ESP32_SD_TFT_MOSI") (class "Default")
      (node (ref "J4") (pin "3") (pinfunction "CMD_3") (pintype "bidirectional"))
      (node (ref "K1") (pin "19") (pinfunction "19_19") (pintype "passive"))
      (node (ref "U4") (pin "21") (pinfunction "IO7_21") (pintype "bidirectional"))
      (node (ref "U7") (pin "14") (pinfunction "GPIO11_14") (pintype "bidirectional"))
    )
    (net (code "19") (name "ESP32_SD_TFT_SCK") (class "Default")
      (node (ref "J4") (pin "5") (pinfunction "CLK_5") (pintype "bidirectional"))
      (node (ref "K1") (pin "23") (pinfunction "23_23") (pintype "passive"))
      (node (ref "U4") (pin "20") (pinfunction "IO6_20") (pintype "bidirectional"))
      (node (ref "U7") (pin "13") (pinfunction "GPIO10_13") (pintype "bidirectional"))
    )
    (net (code "20") (name "ESP32_UART_RXD") (class "Default")
      (node (ref "R37") (pin "2") (pinfunction "2_2") (pintype "passive"))
      (node (ref "U4") (pin "30") (pinfunction "RXD0_30") (pintype "bidirectional"))
    )
    (net (code "21") (name "ESP32_UART_TXD") (class "Default")
      (node (ref "R36") (pin "2") (pinfunction "2_2") (pintype "passive"))
      (node (ref "U4") (pin "31") (pinfunction "TXD0_31") (pintype "bidirectional"))
    )
    (net (code "22") (name "ESP_BOOT") (class "Default")
      (node (ref "SW1") (pin "B'") (pinfunction "S1_B'") (pintype "passive"))
      (node (ref "U4") (pin "23") (pinfunction "IO9_23") (pintype "bidirectional"))
    )
    (net (code "23") (name "ESP_RST") (class "Default")
      (node (ref "C4") (pin "2") (pinfunction "2_2") (pintype "passive"))
      (node (ref "R23") (pin "1") (pinfunction "1_1") (pintype "passive"))
      (node (ref "SW2") (pin "B'") (pinfunction "S1_B'") (pintype "passive"))
      (node (ref "U4") (pin "8") (pinfunction "EN_8") (pintype "input"))
    )
    (net (code "24") (name "FCLK") (class "Default")
      (node (ref "TP2") (pin "P$1") (pinfunction "1_P$1") (pintype "bidirectional"))
      (node (ref "U$30") (pin "D5") (pinfunction "FCLK_D5") (pintype "bidirectional"))
      (node (ref "U$31") (pin "3") (pinfunction "CLK_3") (pintype "bidirectional"))
    )
    (net (code "25") (name "GND") (class "Default")
      (node (ref "C1") (pin "2") (pinfunction "2_2") (pintype "passive"))
      (node (ref "C10") (pin "2") (pinfunction "2_2") (pintype "passive"))
      (node (ref "C11") (pin "2") (pinfunction "2_2") (pintype "passive"))
      (node (ref "C12") (pin "2") (pinfunction "2_2") (pintype "passive"))
      (node (ref "C13") (pin "2") (pinfunction "2_2") (pintype "passive"))
      (node (ref "C14") (pin "2") (pinfunction "2_2") (pintype "passive"))
      (node (ref "C15") (pin "1") (pinfunction "1_1") (pintype "passive"))
      (node (ref "C18") (pin "2") (pinfunction "2_2") (pintype "passive"))
      (node (ref "C19") (pin "2") (pinfunction "2_2") (pintype "passive"))
      (node (ref "C2") (pin "2") (pinfunction "2_2") (pintype "passive"))
      (node (ref "C22") (pin "2") (pinfunction "2_2") (pintype "passive"))
      (node (ref "C24") (pin "2") (pinfunction "2_2") (pintype "passive"))
      (node (ref "C25") (pin "2") (pinfunction "2_2") (pintype "passive"))
      (node (ref "C27") (pin "2") (pinfunction "2_2") (pintype "passive"))
      (node (ref "C28") (pin "2") (pinfunction "2_2") (pintype "passive"))
      (node (ref "C29") (pin "2") (pinfunction "2_2") (pintype "passive"))
      (node (ref "C3") (pin "1") (pinfunction "1_1") (pintype "passive"))
      (node (ref "C30") (pin "2") (pinfunction "2_2") (pintype "passive"))
      (node (ref "C31") (pin "1") (pinfunction "1_1") (pintype "passive"))
      (node (ref "C32") (pin "2") (pinfunction "2_2") (pintype "passive"))
      (node (ref "C33") (pin "2") (pinfunction "2_2") (pintype "passive"))
      (node (ref "C34") (pin "2") (pinfunction "2_2") (pintype "passive"))
      (node (ref "C35") (pin "1") (pinfunction "1_1") (pintype "passive"))
      (node (ref "C36") (pin "1") (pinfunction "1_1") (pintype "passive"))
      (node (ref "C37") (pin "1") (pinfunction "1_1") (pintype "passive"))
      (node (ref "C38") (pin "2") (pinfunction "2_2") (pintype "passive"))
      (node (ref "C39") (pin "2") (pinfunction "2_2") (pintype "passive"))
      (node (ref "C4") (pin "1") (pinfunction "1_1") (pintype "passive"))
      (node (ref "C40") (pin "2") (pinfunction "2_2") (pintype "passive"))
      (node (ref "C41") (pin "2") (pinfunction "2_2") (pintype "passive"))
      (node (ref "C42") (pin "2") (pinfunction "2_2") (pintype "passive"))
      (node (ref "C43") (pin "2") (pinfunction "2_2") (pintype "passive"))
      (node (ref "C44") (pin "2") (pinfunction "2_2") (pintype "passive"))
      (node (ref "C46") (pin "2") (pinfunction "2_2") (pintype "passive"))
      (node (ref "C47") (pin "2") (pinfunction "2_2") (pintype "passive"))
      (node (ref "C48") (pin "2") (pinfunction "2_2") (pintype "passive"))
      (node (ref "C49") (pin "2") (pinfunction "2_2") (pintype "passive"))
      (node (ref "C50") (pin "2") (pinfunction "2_2") (pintype "passive"))
      (node (ref "C51") (pin "2") (pinfunction "2_2") (pintype "passive"))
      (node (ref "C52") (pin "2") (pinfunction "2_2") (pintype "passive"))
      (node (ref "C53") (pin "2") (pinfunction "2_2") (pintype "passive"))
      (node (ref "C59") (pin "2") (pinfunction "2_2") (pintype "passive"))
      (node (ref "C6") (pin "1") (pinfunction "1_1") (pintype "passive"))
      (node (ref "C64") (pin "2") (pinfunction "2_2") (pintype "passive"))
      (node (ref "C65") (pin "2") (pinfunction "2_2") (pintype "passive"))
      (node (ref "C67") (pin "2") (pinfunction "2_2") (pintype "passive"))
      (node (ref "C68") (pin "2") (pinfunction "2_2") (pintype "passive"))
      (node (ref "C7") (pin "1") (pinfunction "1_1") (pintype "passive"))
      (node (ref "C70") (pin "2") (pinfunction "P$2_2") (pintype "passive"))
      (node (ref "C8") (pin "2") (pinfunction "2_2") (pintype "passive"))
      (node (ref "C9") (pin "2") (pinfunction "2_2") (pintype "passive"))
      (node (ref "D1") (pin "2") (pinfunction "C_2") (pintype "passive"))
      (node (ref "D2") (pin "2") (pinfunction "C_2") (pintype "passive"))
      (node (ref "D3") (pin "2") (pinfunction "C_2") (pintype "passive"))
      (node (ref "D5") (pin "2") (pinfunction "C_2") (pintype "passive"))
      (node (ref "J1") (pin "1") (pinfunction "1_1") (pintype "power_in"))
      (node (ref "J2") (pin "1") (pinfunction "1_1") (pintype "power_in"))
      (node (ref "J3") (pin "GND") (pinfunction "GND_GND") (pintype "bidirectional"))
      (node (ref "J3") (pin "GND2") (pinfunction "GND_GND2") (pintype "bidirectional"))
      (node (ref "J3") (pin "SHLD1") (pinfunction "SHLD_SHLD1") (pintype "bidirectional"))
      (node (ref "J3") (pin "SHLD2") (pinfunction "SHLD_SHLD2") (pintype "bidirectional"))
      (node (ref "J3") (pin "SHLD3") (pinfunction "SHLD_SHLD3") (pintype "bidirectional"))
      (node (ref "J3") (pin "SHLD4") (pinfunction "SHLD_SHLD4") (pintype "bidirectional"))
      (node (ref "J3") (pin "SHLD5") (pinfunction "SHLD_SHLD5") (pintype "bidirectional"))
      (node (ref "J3") (pin "SHLD6") (pinfunction "SHLD_SHLD6") (pintype "bidirectional"))
      (node (ref "J3") (pin "SHLD7") (pinfunction "SHLD_SHLD7") (pintype "bidirectional"))
      (node (ref "J3") (pin "SHLD8") (pinfunction "SHLD_SHLD8") (pintype "bidirectional"))
      (node (ref "J4") (pin "6") (pinfunction "VSS_6") (pintype "power_in"))
      (node (ref "J5") (pin "GND") (pinfunction "GND_GND") (pintype "bidirectional"))
      (node (ref "J5") (pin "GND2") (pinfunction "GND_GND2") (pintype "bidirectional"))
      (node (ref "J5") (pin "SHLD1") (pinfunction "SHLD_SHLD1") (pintype "bidirectional"))
      (node (ref "J5") (pin "SHLD2") (pinfunction "SHLD_SHLD2") (pintype "bidirectional"))
      (node (ref "J5") (pin "SHLD3") (pinfunction "SHLD_SHLD3") (pintype "bidirectional"))
      (node (ref "J5") (pin "SHLD4") (pinfunction "SHLD_SHLD4") (pintype "bidirectional"))
      (node (ref "J5") (pin "SHLD5") (pinfunction "SHLD_SHLD5") (pintype "bidirectional"))
      (node (ref "J5") (pin "SHLD6") (pinfunction "SHLD_SHLD6") (pintype "bidirectional"))
      (node (ref "J5") (pin "SHLD7") (pinfunction "SHLD_SHLD7") (pintype "bidirectional"))
      (node (ref "J5") (pin "SHLD8") (pinfunction "SHLD_SHLD8") (pintype "bidirectional"))
      (node (ref "JP6") (pin "1") (pinfunction "1_1") (pintype "passive"))
      (node (ref "K1") (pin "14") (pinfunction "14_14") (pintype "passive"))
      (node (ref "K1") (pin "20") (pinfunction "20_20") (pintype "passive"))
      (node (ref "K1") (pin "25") (pinfunction "25_25") (pintype "passive"))
      (node (ref "K1") (pin "30") (pinfunction "30_30") (pintype "passive"))
      (node (ref "K1") (pin "34") (pinfunction "34_34") (pintype "passive"))
      (node (ref "K1") (pin "39") (pinfunction "39_39") (pintype "passive"))
      (node (ref "K1") (pin "6") (pinfunction "6_6") (pintype "passive"))
      (node (ref "K1") (pin "9") (pinfunction "9_9") (pintype "passive"))
      (node (ref "R1") (pin "1") (pinfunction "1_1") (pintype "passive"))
      (node (ref "R11") (pin "1") (pinfunction "1_1") (pintype "passive"))
      (node (ref "R14") (pin "1") (pinfunction "1_1") (pintype "passive"))
      (node (ref "R15") (pin "2") (pinfunction "2_2") (pintype "passive"))
      (node (ref "R16") (pin "2") (pinfunction "2_2") (pintype "passive"))
      (node (ref "R26") (pin "2") (pinfunction "2_2") (pintype "passive"))
      (node (ref "R27") (pin "2") (pinfunction "2_2") (pintype "passive"))
      (node (ref "R30") (pin "1") (pinfunction "1_1") (pintype "passive"))
      (node (ref "R44") (pin "2") (pinfunction "2_2") (pintype "passive"))
      (node (ref "SW1") (pin "A'") (pinfunction "P1_A'") (pintype "passive"))
      (node (ref "SW2") (pin "A'") (pinfunction "P1_A'") (pintype "passive"))
      (node (ref "SW4") (pin "A'") (pinfunction "P1_A'") (pintype "passive"))
      (node (ref "SW5") (pin "A'") (pinfunction "P1_A'") (pintype "passive"))
      (node (ref "TP1") (pin "TP") (pinfunction "TP_TP") (pintype "input"))
      (node (ref "U$26") (pin "2") (pinfunction "GND_2") (pintype "bidirectional"))
      (node (ref "U$3") (pin "12") (pinfunction "LED_DRV_GND_12") (pintype "bidirectional"))
      (node (ref "U$3") (pin "13") (pinfunction "LED_DRV_GND_13") (pintype "bidirectional"))
      (node (ref "U$3") (pin "16") (pinfunction "LED_DRV_GND_16") (pintype "bidirectional"))
      (node (ref "U$3") (pin "19") (pinfunction "RX_DIG_GND_19") (pintype "bidirectional"))
      (node (ref "U$3") (pin "3") (pinfunction "RX_ANA_GND_3") (pintype "bidirectional"))
      (node (ref "U$3") (pin "32") (pinfunction "RX_DIG_GND_32") (pintype "bidirectional"))
      (node (ref "U$3") (pin "36") (pinfunction "RX_ANA_GND_36") (pintype "bidirectional"))
      (node (ref "U$3") (pin "40") (pinfunction "RX_ANA_GND_40") (pintype "bidirectional"))
      (node (ref "U$3") (pin "8") (pinfunction "VSS_8") (pintype "bidirectional"))
      (node (ref "U$3") (pin "EXP@10") (pinfunction "THER3_EXP@10") (pintype "bidirectional"))
      (node (ref "U$3") (pin "EXP@11") (pinfunction "THER4_EXP@11") (pintype "bidirectional"))
      (node (ref "U$3") (pin "EXP@6") (pinfunction "THER1_EXP@6") (pintype "bidirectional"))
      (node (ref "U$3") (pin "EXP@7") (pinfunction "THER2_EXP@7") (pintype "bidirectional"))
      (node (ref "U$30") (pin "B3") (pinfunction "AGND_B3") (pintype "bidirectional"))
      (node (ref "U$30") (pin "B4") (pinfunction "AGND_B4") (pintype "bidirectional"))
      (node (ref "U$30") (pin "C3") (pinfunction "AGND_C3") (pintype "bidirectional"))
      (node (ref "U$30") (pin "C4") (pinfunction "AGND_C4") (pintype "bidirectional"))
      (node (ref "U$30") (pin "C5") (pinfunction "DGND_C5") (pintype "bidirectional"))
      (node (ref "U$30") (pin "D4") (pinfunction "AGND_D4") (pintype "bidirectional"))
      (node (ref "U$31") (pin "2") (pinfunction "GND_2") (pintype "bidirectional"))
      (node (ref "U3") (pin "2") (pinfunction "GND_2") (pintype "input"))
      (node (ref "U4") (pin "1") (pinfunction "GND_1") (pintype "power_in"))
      (node (ref "U4") (pin "11") (pinfunction "GND_11") (pintype "power_in"))
      (node (ref "U4") (pin "14") (pinfunction "GND_14") (pintype "power_in"))
      (node (ref "U4") (pin "2") (pinfunction "GND_2") (pintype "power_in"))
      (node (ref "U4") (pin "36") (pinfunction "GND_36") (pintype "power_in"))
      (node (ref "U4") (pin "37") (pinfunction "GND_37") (pintype "power_in"))
      (node (ref "U4") (pin "38") (pinfunction "GND_38") (pintype "power_in"))
      (node (ref "U4") (pin "39") (pinfunction "GND_39") (pintype "power_in"))
      (node (ref "U4") (pin "40") (pinfunction "GND_40") (pintype "power_in"))
      (node (ref "U4") (pin "41") (pinfunction "GND_41") (pintype "power_in"))
      (node (ref "U4") (pin "42") (pinfunction "GND_42") (pintype "power_in"))
      (node (ref "U4") (pin "43") (pinfunction "GND_43") (pintype "power_in"))
      (node (ref "U4") (pin "44") (pinfunction "GND_44") (pintype "power_in"))
      (node (ref "U4") (pin "45") (pinfunction "GND_45") (pintype "power_in"))
      (node (ref "U4") (pin "46") (pinfunction "GND_46") (pintype "power_in"))
      (node (ref "U4") (pin "47") (pinfunction "GND_47") (pintype "power_in"))
      (node (ref "U4") (pin "48") (pinfunction "GND_48") (pintype "power_in"))
      (node (ref "U4") (pin "49_1") (pinfunction "GND_49_1") (pintype "power_in"))
      (node (ref "U4") (pin "49_2") (pinfunction "GND_49_2") (pintype "power_in"))
      (node (ref "U4") (pin "49_3") (pinfunction "GND_49_3") (pintype "power_in"))
      (node (ref "U4") (pin "49_4") (pinfunction "GND_49_4") (pintype "power_in"))
      (node (ref "U4") (pin "49_5") (pinfunction "GND_49_5") (pintype "power_in"))
      (node (ref "U4") (pin "49_6") (pinfunction "GND_49_6") (pintype "power_in"))
      (node (ref "U4") (pin "49_7") (pinfunction "GND_49_7") (pintype "power_in"))
      (node (ref "U4") (pin "49_8") (pinfunction "GND_49_8") (pintype "power_in"))
      (node (ref "U4") (pin "49_9") (pinfunction "GND_49_9") (pintype "power_in"))
      (node (ref "U4") (pin "50") (pinfunction "GND_50") (pintype "power_in"))
      (node (ref "U4") (pin "51") (pinfunction "GND_51") (pintype "power_in"))
      (node (ref "U4") (pin "52") (pinfunction "GND_52") (pintype "power_in"))
      (node (ref "U4") (pin "53") (pinfunction "GND_53") (pintype "power_in"))
      (node (ref "U5") (pin "2") (pinfunction "VSS_2") (pintype "power_in"))
      (node (ref "U6") (pin "4") (pinfunction "GND_4") (pintype "bidirectional"))
      (node (ref "U7") (pin "19") (pinfunction "TESTEN_19") (pintype "bidirectional"))
      (node (ref "U7") (pin "EPAD") (pinfunction "GND_EPAD") (pintype "bidirectional"))
      (node (ref "X1") (pin "7") (pinfunction "7_7") (pintype "passive"))
      (node (ref "X1") (pin "G1") (pinfunction "P$1_G1") (pintype "bidirectional"))
      (node (ref "X1") (pin "G2") (pinfunction "P$2_G2") (pintype "bidirectional"))
    )
    (net (code "26") (name "INN") (class "Default")
      (node (ref "D3") (pin "1") (pinfunction "CA_1") (pintype "passive"))
      (node (ref "U$3") (pin "1") (pinfunction "INN_1") (pintype "bidirectional"))
      (node (ref "X1") (pin "5") (pinfunction "5_5") (pintype "passive"))
    )
    (net (code "27") (name "INP") (class "Default")
      (node (ref "D2") (pin "1") (pinfunction "CA_1") (pintype "passive"))
      (node (ref "U$3") (pin "2") (pinfunction "INP_2") (pintype "bidirectional"))
      (node (ref "X1") (pin "9") (pinfunction "9_9") (pintype "passive"))
    )
    (net (code "28") (name "INT2B") (class "Default")
      (node (ref "U$30") (pin "E2") (pinfunction "INT2B_E2") (pintype "bidirectional"))
      (node (ref "U7") (pin "30") (pinfunction "GPIO19_30") (pintype "bidirectional"))
    )
    (net (code "29") (name "INTB") (class "Default")
      (node (ref "U$30") (pin "D2") (pinfunction "INTB_D2") (pintype "bidirectional"))
      (node (ref "U7") (pin "31") (pinfunction "GPIO20_31") (pintype "bidirectional"))
    )
    (net (code "30") (name "LED1") (class "Default")
      (node (ref "R51") (pin "2") (pinfunction "2_2") (pintype "passive"))
      (node (ref "U7") (pin "34") (pinfunction "GPIO22_34") (pintype "bidirectional"))
    )
    (net (code "31") (name "LED2") (class "Default")
      (node (ref "R49") (pin "1") (pinfunction "1_1") (pintype "passive"))
      (node (ref "U7") (pin "32") (pinfunction "GPIO21_32") (pintype "bidirectional"))
    )
    (net (code "32") (name "LED_DRV_SUP") (class "Default")
      (node (ref "C10") (pin "1") (pinfunction "1_1") (pintype "passive"))
      (node (ref "C28") (pin "1") (pinfunction "1_1") (pintype "passive"))
      (node (ref "D1") (pin "3") (pinfunction "A_3") (pintype "passive"))
      (node (ref "D5") (pin "3") (pinfunction "A_3") (pintype "passive"))
      (node (ref "U$11") (pin "2") (pinfunction "P$2_2") (pintype "bidirectional"))
      (node (ref "U$3") (pin "17") (pinfunction "LED_DRV_SUP_17") (pintype "bidirectional"))
      (node (ref "U$3") (pin "18") (pinfunction "LED_DRV_SUP_18") (pintype "bidirectional"))
    )
    (net (code "33") (name "MISO") (class "Default")
      (node (ref "U$3") (pin "25") (pinfunction "SPISOMI_25") (pintype "bidirectional"))
      (node (ref "U$30") (pin "E3") (pinfunction "SDO_E3") (pintype "bidirectional"))
      (node (ref "U7") (pin "6") (pinfunction "GPIO4_6") (pintype "bidirectional"))
    )
    (net (code "34") (name "MOSI") (class "Default")
      (node (ref "U$3") (pin "26") (pinfunction "SPISIMO_26") (pintype "bidirectional"))
      (node (ref "U$30") (pin "E4") (pinfunction "SDI_E4") (pintype "bidirectional"))
      (node (ref "U7") (pin "5") (pinfunction "GPIO3_5") (pintype "bidirectional"))
    )
    (net (code "35") (name "Net-(J3-CC1)") (class "Default")
      (node (ref "J3") (pin "A5") (pinfunction "CC1_A5") (pintype "bidirectional"))
      (node (ref "R27") (pin "1") (pinfunction "1_1") (pintype "passive"))
    )
    (net (code "36") (name "Net-(J3-CC2)") (class "Default")
      (node (ref "J3") (pin "B5") (pinfunction "CC2_B5") (pintype "bidirectional"))
      (node (ref "R26") (pin "1") (pinfunction "1_1") (pintype "passive"))
    )
    (net (code "37") (name "Net-(J5-CC1)") (class "Default")
      (node (ref "J5") (pin "A5") (pinfunction "CC1_A5") (pintype "bidirectional"))
      (node (ref "R16") (pin "1") (pinfunction "1_1") (pintype "passive"))
    )
    (net (code "38") (name "Net-(J5-CC2)") (class "Default")
      (node (ref "J5") (pin "B5") (pinfunction "CC2_B5") (pintype "bidirectional"))
      (node (ref "R15") (pin "1") (pinfunction "1_1") (pintype "passive"))
    )
    (net (code "39") (name "Net-(J5-D+-PadA6)") (class "Default")
      (node (ref "J5") (pin "A6") (pinfunction "D+_A6") (pintype "bidirectional"))
      (node (ref "J5") (pin "B6") (pinfunction "D+_B6") (pintype "bidirectional"))
      (node (ref "R8") (pin "1") (pinfunction "1_1") (pintype "passive"))
    )
    (net (code "40") (name "Net-(J5-D--PadA7)") (class "Default")
      (node (ref "J5") (pin "A7") (pinfunction "D-_A7") (pintype "bidirectional"))
      (node (ref "J5") (pin "B7") (pinfunction "D-_B7") (pintype "bidirectional"))
      (node (ref "R10") (pin "1") (pinfunction "1_1") (pintype "passive"))
    )
    (net (code "41") (name "Net-(JP3-PadSLEEVE)") (class "Default")
      (node (ref "JP3") (pin "SLEEVE") (pinfunction "SLEEVE_SLEEVE") (pintype "bidirectional"))
      (node (ref "R41") (pin "2") (pinfunction "2_2") (pintype "passive"))
    )
    (net (code "42") (name "Net-(JP_SW3-Pad3)") (class "Default")
      (node (ref "JP_SW3") (pin "3") (pinfunction "3_3") (pintype "passive"))
      (node (ref "K1") (pin "16") (pinfunction "16_16") (pintype "passive"))
    )
    (net (code "43") (name "Net-(LED1-0)") (class "Default")
      (node (ref "LED1") (pin "1") (pinfunction "0_1") (pintype "passive"))
      (node (ref "LED1") (pin "2") (pinfunction "1_2") (pintype "passive"))
      (node (ref "R49") (pin "2") (pinfunction "2_2") (pintype "passive"))
    )
    (net (code "44") (name "Net-(LED1-3)") (class "Default")
      (node (ref "LED1") (pin "4") (pinfunction "3_4") (pintype "passive"))
      (node (ref "R48") (pin "2") (pinfunction "2_2") (pintype "passive"))
    )
    (net (code "45") (name "Net-(LED1-5)") (class "Default")
      (node (ref "LED1") (pin "6") (pinfunction "5_6") (pintype "passive"))
      (node (ref "R51") (pin "1") (pinfunction "1_1") (pintype "passive"))
    )
    (net (code "46") (name "Net-(Q3-S)") (class "Default")
      (node (ref "C22") (pin "1") (pinfunction "1_1") (pintype "passive"))
      (node (ref "C37") (pin "2") (pinfunction "2_2") (pintype "passive"))
      (node (ref "D10") (pin "C") (pinfunction "C_C") (pintype "passive"))
      (node (ref "Q3") (pin "2") (pinfunction "S_2") (pintype "passive"))
      (node (ref "S2") (pin "3") (pinfunction "3_3") (pintype "bidirectional"))
      (node (ref "U$26") (pin "1") (pinfunction "VIN_1") (pintype "bidirectional"))
      (node (ref "U3") (pin "1") (pinfunction "IN_1") (pintype "input"))
    )
    (net (code "47") (name "Net-(R1-Pad2)") (class "Default")
      (node (ref "R1") (pin "2") (pinfunction "2_2") (pintype "passive"))
      (node (ref "S2") (pin "1") (pinfunction "1_1") (pintype "bidirectional"))
    )
    (net (code "48") (name "Net-(TP4-1)") (class "Default")
      (node (ref "TP4") (pin "P$1") (pinfunction "1_P$1") (pintype "bidirectional"))
      (node (ref "U$3") (pin "30") (pinfunction "CLKOUT_30") (pintype "bidirectional"))
    )
    (net (code "49") (name "Net-(U$3-BG)") (class "Default")
      (node (ref "C8") (pin "1") (pinfunction "1_1") (pintype "passive"))
      (node (ref "U$3") (pin "7") (pinfunction "BG_7") (pintype "bidirectional"))
    )
    (net (code "50") (name "Net-(U$3-XIN)") (class "Default")
      (node (ref "C6") (pin "2") (pinfunction "2_2") (pintype "passive"))
      (node (ref "U$3") (pin "38") (pinfunction "XIN_38") (pintype "bidirectional"))
      (node (ref "U$4") (pin "2") (pinfunction "2_2") (pintype "passive"))
    )
    (net (code "51") (name "Net-(U$3-XOUT)") (class "Default")
      (node (ref "C7") (pin "2") (pinfunction "2_2") (pintype "passive"))
      (node (ref "U$3") (pin "37") (pinfunction "XOUT_37") (pintype "bidirectional"))
      (node (ref "U$4") (pin "1") (pinfunction "1_1") (pintype "passive"))
    )
    (net (code "52") (name "Net-(U$19-1)") (class "Default")
      (node (ref "C1") (pin "1") (pinfunction "1_1") (pintype "passive"))
      (node (ref "U$19") (pin "P$1") (pinfunction "1_P$1") (pintype "passive"))
      (node (ref "U4") (pin "13") (pinfunction "IO1_13") (pintype "bidirectional"))
    )
    (net (code "53") (name "Net-(U$19-2)") (class "Default")
      (node (ref "C15") (pin "2") (pinfunction "2_2") (pintype "passive"))
      (node (ref "U$19") (pin "P$2") (pinfunction "2_P$2") (pintype "passive"))
      (node (ref "U4") (pin "12") (pinfunction "IO0_12") (pintype "bidirectional"))
    )
    (net (code "54") (name "Net-(U$30-BIN)") (class "Default")
      (node (ref "C67") (pin "1") (pinfunction "1_1") (pintype "passive"))
      (node (ref "C69") (pin "1") (pinfunction "1_1") (pintype "passive"))
      (node (ref "R42") (pin "2") (pinfunction "2_2") (pintype "passive"))
      (node (ref "U$30") (pin "A3") (pinfunction "BIN_A3") (pintype "bidirectional"))
    )
    (net (code "55") (name "Net-(U$30-BIP)") (class "Default")
      (node (ref "C68") (pin "1") (pinfunction "1_1") (pintype "passive"))
      (node (ref "C69") (pin "2") (pinfunction "2_2") (pintype "passive"))
      (node (ref "R43") (pin "2") (pinfunction "2_2") (pintype "passive"))
      (node (ref "U$30") (pin "A4") (pinfunction "BIP_A4") (pintype "bidirectional"))
    )
    (net (code "56") (name "Net-(U$30-CAPN)") (class "Default")
      (node (ref "C26") (pin "2") (pinfunction "2_2") (pintype "passive"))
      (node (ref "U$30") (pin "B5") (pinfunction "CAPN_B5") (pintype "bidirectional"))
    )
    (net (code "57") (name "Net-(U$30-CAPP)") (class "Default")
      (node (ref "C26") (pin "1") (pinfunction "1_1") (pintype "passive"))
      (node (ref "U$30") (pin "B6") (pinfunction "CAPP_B6") (pintype "bidirectional"))
    )
    (net (code "58") (name "Net-(U$30-CPLL)") (class "Default")
      (node (ref "C29") (pin "1") (pinfunction "1_1") (pintype "passive"))
      (node (ref "U$30") (pin "C6") (pinfunction "CPLL_C6") (pintype "bidirectional"))
    )
    (net (code "59") (name "Net-(U$30-DRVN)") (class "Default")
      (node (ref "C66") (pin "2") (pinfunction "2_2") (pintype "passive"))
      (node (ref "U$30") (pin "A2") (pinfunction "DRVN_A2") (pintype "bidirectional"))
    )
    (net (code "60") (name "Net-(U$30-DRVP)") (class "Default")
      (node (ref "C63") (pin "2") (pinfunction "2_2") (pintype "passive"))
      (node (ref "U$30") (pin "A1") (pinfunction "DRVP_A1") (pintype "bidirectional"))
    )
    (net (code "61") (name "Net-(U$30-RBIAS)") (class "Default")
      (node (ref "R44") (pin "1") (pinfunction "1_1") (pintype "passive"))
      (node (ref "U$30") (pin "B2") (pinfunction "RBIAS_B2") (pintype "bidirectional"))
    )
    (net (code "62") (name "Net-(U$30-VBG)") (class "Default")
      (node (ref "C34") (pin "1") (pinfunction "1_1") (pintype "passive"))
      (node (ref "U$30") (pin "B1") (pinfunction "VBG_B1") (pintype "bidirectional"))
    )
    (net (code "63") (name "Net-(U$30-VREF)") (class "Default")
      (node (ref "C32") (pin "1") (pinfunction "1_1") (pintype "passive"))
      (node (ref "U$30") (pin "D1") (pinfunction "VREF_D1") (pintype "bidirectional"))
    )
    (net (code "64") (name "Net-(U4-IO2)") (class "Default")
      (node (ref "R2") (pin "2") (pinfunction "2_2") (pintype "passive"))
      (node (ref "U4") (pin "5") (pinfunction "IO2_5") (pintype "bidirectional"))
    )
    (net (code "65") (name "Net-(U4-IO3)") (class "Default")
      (node (ref "SWIO3") (pin "TP") (pinfunction "TP_TP") (pintype "input"))
      (node (ref "U4") (pin "6") (pinfunction "IO3_6") (pintype "bidirectional"))
    )
    (net (code "66") (name "Net-(U4-IO4)") (class "Default")
      (node (ref "SWIO4") (pin "TP") (pinfunction "TP_TP") (pintype "input"))
      (node (ref "U4") (pin "18") (pinfunction "IO4_18") (pintype "bidirectional"))
    )
    (net (code "67") (name "Net-(U4-IO5)") (class "Default")
      (node (ref "SWIO6") (pin "TP") (pinfunction "TP_TP") (pintype "input"))
      (node (ref "U4") (pin "19") (pinfunction "IO5_19") (pintype "bidirectional"))
    )
    (net (code "68") (name "Net-(U4-IO8)") (class "Default")
      (node (ref "SWIO2") (pin "TP") (pinfunction "TP_TP") (pintype "input"))
      (node (ref "U4") (pin "22") (pinfunction "IO8_22") (pintype "bidirectional"))
    )
    (net (code "69") (name "Net-(U5-PROG)") (class "Default")
      (node (ref "R11") (pin "2") (pinfunction "2_2") (pintype "passive"))
      (node (ref "U5") (pin "5") (pinfunction "PROG_5") (pintype "input"))
    )
    (net (code "70") (name "Net-(U7-GPIO24)") (class "Default")
      (node (ref "R37") (pin "1") (pinfunction "1_1") (pintype "passive"))
      (node (ref "U7") (pin "36") (pinfunction "GPIO24_36") (pintype "bidirectional"))
    )
    (net (code "71") (name "Net-(U7-GPIO25)") (class "Default")
      (node (ref "R36") (pin "1") (pinfunction "1_1") (pintype "passive"))
      (node (ref "U7") (pin "37") (pinfunction "GPIO25_37") (pintype "bidirectional"))
    )
    (net (code "72") (name "Net-(U7-USB_D+)") (class "Default")
      (node (ref "R20") (pin "2") (pinfunction "2_2") (pintype "passive"))
      (node (ref "U7") (pin "47") (pinfunction "USB_D+_47") (pintype "bidirectional"))
    )
    (net (code "73") (name "Net-(U7-USB_D-)") (class "Default")
      (node (ref "R19") (pin "2") (pinfunction "2_2") (pintype "passive"))
      (node (ref "U7") (pin "46") (pinfunction "USB_D-_46") (pintype "bidirectional"))
    )
    (net (code "74") (name "Net-(U7-XIN)") (class "Default")
      (node (ref "C36") (pin "2") (pinfunction "2_2") (pintype "passive"))
      (node (ref "U7") (pin "20") (pinfunction "XIN_20") (pintype "bidirectional"))
      (node (ref "Y2") (pin "P3") (pinfunction "2_P3") (pintype "passive"))
    )
    (net (code "75") (name "Net-(U7-XOUT)") (class "Default")
      (node (ref "R18") (pin "2") (pinfunction "2_2") (pintype "passive"))
      (node (ref "U7") (pin "21") (pinfunction "XOUT_21") (pintype "bidirectional"))
    )
    (net (code "76") (name "Net-(Y2-1)") (class "Default")
      (node (ref "C31") (pin "2") (pinfunction "2_2") (pintype "passive"))
      (node (ref "R18") (pin "1") (pinfunction "1_1") (pintype "passive"))
      (node (ref "Y2") (pin "P1") (pinfunction "1_P1") (pintype "passive"))
    )
    (net (code "77") (name "QSPI-0") (class "Default")
      (node (ref "U6") (pin "5") (pinfunction "D0/DI_5") (pintype "bidirectional"))
      (node (ref "U7") (pin "53") (pinfunction "QSPI_SD0_53") (pintype "bidirectional"))
    )
    (net (code "78") (name "QSPI-1") (class "Default")
      (node (ref "U6") (pin "2") (pinfunction "D1/DO_2") (pintype "bidirectional"))
      (node (ref "U7") (pin "55") (pinfunction "QSPI_SD1_55") (pintype "bidirectional"))
    )
    (net (code "79") (name "QSPI-2") (class "Default")
      (node (ref "U6") (pin "3") (pinfunction "D2/~{WP}_3") (pintype "bidirectional"))
      (node (ref "U7") (pin "54") (pinfunction "QSPI_SD2_54") (pintype "bidirectional"))
    )
    (net (code "80") (name "QSPI-3") (class "Default")
      (node (ref "U6") (pin "7") (pinfunction "D3/~{HOLD}_7") (pintype "bidirectional"))
      (node (ref "U7") (pin "51") (pinfunction "QSPI_SD3_51") (pintype "bidirectional"))
    )
    (net (code "81") (name "QSPI-CLK") (class "Default")
      (node (ref "U6") (pin "6") (pinfunction "CLK_6") (pintype "bidirectional"))
      (node (ref "U7") (pin "52") (pinfunction "QSPI_SCLK_52") (pintype "bidirectional"))
    )
    (net (code "82") (name "QSPI-CS") (class "Default")
      (node (ref "R21") (pin "1") (pinfunction "1_1") (pintype "passive"))
      (node (ref "R22") (pin "1") (pinfunction "1_1") (pintype "passive"))
      (node (ref "U6") (pin "1") (pinfunction "~{CS}_1") (pintype "bidirectional"))
      (node (ref "U7") (pin "56") (pinfunction "QSPI_~{CS}_56") (pintype "bidirectional"))
    )
    (net (code "83") (name "RP_D+") (class "Default")
      (node (ref "J3") (pin "A6") (pinfunction "D+_A6") (pintype "bidirectional"))
      (node (ref "J3") (pin "B6") (pinfunction "D+_B6") (pintype "bidirectional"))
      (node (ref "R20") (pin "1") (pinfunction "1_1") (pintype "passive"))
    )
    (net (code "84") (name "RP_D-") (class "Default")
      (node (ref "J3") (pin "A7") (pinfunction "D-_A7") (pintype "bidirectional"))
      (node (ref "J3") (pin "B7") (pinfunction "D-_B7") (pintype "bidirectional"))
      (node (ref "R19") (pin "1") (pinfunction "1_1") (pintype "passive"))
    )
    (net (code "85") (name "RX_ANA_SUP") (class "Default")
      (node (ref "C11") (pin "1") (pinfunction "1_1") (pintype "passive"))
      (node (ref "C18") (pin "1") (pinfunction "1_1") (pintype "passive"))
      (node (ref "D2") (pin "3") (pinfunction "A_3") (pintype "passive"))
      (node (ref "D3") (pin "3") (pinfunction "A_3") (pintype "passive"))
      (node (ref "U$3") (pin "33") (pinfunction "RX_ANA_SUP_33") (pintype "bidirectional"))
      (node (ref "U$3") (pin "39") (pinfunction "RX_ANA_SUP_39") (pintype "bidirectional"))
      (node (ref "U$7") (pin "2") (pinfunction "P$2_2") (pintype "bidirectional"))
    )
    (net (code "86") (name "RX_DIG_SUP") (class "Default")
      (node (ref "C12") (pin "1") (pinfunction "1_1") (pintype "passive"))
      (node (ref "C19") (pin "1") (pinfunction "1_1") (pintype "passive"))
      (node (ref "R47") (pin "1") (pinfunction "1_1") (pintype "passive"))
      (node (ref "U$3") (pin "31") (pinfunction "RX_DIG_SUP_31") (pintype "bidirectional"))
      (node (ref "U$9") (pin "2") (pinfunction "P$2_2") (pintype "bidirectional"))
    )
    (net (code "87") (name "SCK") (class "Default")
      (node (ref "U$3") (pin "24") (pinfunction "SCLK_24") (pintype "bidirectional"))
      (node (ref "U$30") (pin "E5") (pinfunction "SCLK_E5") (pintype "bidirectional"))
      (node (ref "U7") (pin "4") (pinfunction "GPIO2_4") (pintype "bidirectional"))
    )
    (net (code "88") (name "SD_CS") (class "Default")
      (node (ref "J4") (pin "2") (pinfunction "DATA3/CD_2") (pintype "bidirectional"))
      (node (ref "R5") (pin "1") (pinfunction "1_1") (pintype "passive"))
      (node (ref "U7") (pin "16") (pinfunction "GPIO13_16") (pintype "bidirectional"))
    )
    (net (code "89") (name "SPO2_CS") (class "Default")
      (node (ref "U$3") (pin "27") (pinfunction "SPISTE_27") (pintype "bidirectional"))
      (node (ref "U7") (pin "39") (pinfunction "GPIO27/ADC1_39") (pintype "bidirectional"))
    )
    (net (code "90") (name "SPO2_DRDY") (class "Default")
      (node (ref "U$3") (pin "28") (pinfunction "ADC_RDY_28") (pintype "bidirectional"))
      (node (ref "U7") (pin "28") (pinfunction "GPIO17_28") (pintype "bidirectional"))
    )
    (net (code "91") (name "SPO2_START") (class "Default")
      (node (ref "U$3") (pin "20") (pinfunction "AFE_~{PDN}_20") (pintype "bidirectional"))
      (node (ref "U7") (pin "29") (pinfunction "GPIO18_29") (pintype "bidirectional"))
    )
    (net (code "92") (name "SW1") (class "Default")
      (node (ref "K1") (pin "26") (pinfunction "26_26") (pintype "passive"))
      (node (ref "U7") (pin "15") (pinfunction "GPIO12_15") (pintype "bidirectional"))
    )
    (net (code "93") (name "SW2") (class "Default")
      (node (ref "K1") (pin "31") (pinfunction "31_31") (pintype "passive"))
      (node (ref "U7") (pin "17") (pinfunction "GPIO14_17") (pintype "bidirectional"))
    )
    (net (code "94") (name "SW3") (class "Default")
      (node (ref "JP_SW3") (pin "2") (pinfunction "2_2") (pintype "passive"))
      (node (ref "U7") (pin "18") (pinfunction "GPIO15_18") (pintype "bidirectional"))
    )
    (net (code "95") (name "SWDCK") (class "Default")
      (node (ref "TP6") (pin "TP") (pinfunction "TP_TP") (pintype "input"))
      (node (ref "U7") (pin "24") (pinfunction "SWCLK_24") (pintype "bidirectional"))
    )
    (net (code "96") (name "SWDIO") (class "Default")
      (node (ref "TP7") (pin "TP") (pinfunction "TP_TP") (pintype "input"))
      (node (ref "U7") (pin "25") (pinfunction "SWDIO_25") (pintype "bidirectional"))
    )
    (net (code "97") (name "TFT_BKL") (class "Default")
      (node (ref "K1") (pin "12") (pinfunction "12_12") (pintype "passive"))
      (node (ref "U7") (pin "27") (pinfunction "GPIO16_27") (pintype "bidirectional"))
    )
    (net (code "98") (name "TFT_CS") (class "Default")
      (node (ref "K1") (pin "24") (pinfunction "24_24") (pintype "passive"))
      (node (ref "U7") (pin "41") (pinfunction "GPIO29/ADC3_41") (pintype "bidirectional"))
    )
    (net (code "99") (name "TFT_DC") (class "Default")
      (node (ref "K1") (pin "22") (pinfunction "22_22") (pintype "passive"))
      (node (ref "U7") (pin "35") (pinfunction "GPIO23_35") (pintype "bidirectional"))
    )
    (net (code "100") (name "TFT_RESET") (class "Default")
      (node (ref "K1") (pin "36") (pinfunction "36_36") (pintype "passive"))
      (node (ref "U7") (pin "40") (pinfunction "GPIO28/ADC2_40") (pintype "bidirectional"))
    )
    (net (code "101") (name "TMP_SCL") (class "Default")
      (node (ref "J1") (pin "4") (pinfunction "4_4") (pintype "passive"))
      (node (ref "J2") (pin "4") (pinfunction "4_4") (pintype "passive"))
      (node (ref "R7") (pin "2") (pinfunction "2_2") (pintype "passive"))
      (node (ref "U7") (pin "9") (pinfunction "GPIO7_9") (pintype "bidirectional"))
    )
    (net (code "102") (name "TMP_SDA") (class "Default")
      (node (ref "J1") (pin "3") (pinfunction "3_3") (pintype "passive"))
      (node (ref "J2") (pin "3") (pinfunction "3_3") (pintype "passive"))
      (node (ref "R33") (pin "2") (pinfunction "2_2") (pintype "passive"))
      (node (ref "U7") (pin "8") (pinfunction "GPIO6_8") (pintype "bidirectional"))
    )
    (net (code "103") (name "TXN") (class "Default")
      (node (ref "D1") (pin "1") (pinfunction "CA_1") (pintype "passive"))
      (node (ref "U$3") (pin "14") (pinfunction "TXN_14") (pintype "bidirectional"))
      (node (ref "X1") (pin "3") (pinfunction "3_3") (pintype "passive"))
    )
    (net (code "104") (name "TXP") (class "Default")
      (node (ref "D5") (pin "1") (pinfunction "CA_1") (pintype "passive"))
      (node (ref "U$3") (pin "15") (pinfunction "TXP_15") (pintype "bidirectional"))
      (node (ref "X1") (pin "2") (pinfunction "2_2") (pintype "passive"))
    )
    (net (code "105") (name "TX_CTRL_SUP") (class "Default")
      (node (ref "C27") (pin "1") (pinfunction "1_1") (pintype "passive"))
      (node (ref "C9") (pin "1") (pinfunction "1_1") (pintype "passive"))
      (node (ref "U$10") (pin "2") (pinfunction "P$2_2") (pintype "bidirectional"))
      (node (ref "U$3") (pin "11") (pinfunction "TX_CTRL_SUP_11") (pintype "bidirectional"))
    )
    (net (code "106") (name "U0RXD") (class "Default")
      (node (ref "JP_SW3") (pin "1") (pinfunction "1_1") (pintype "passive"))
      (node (ref "K1") (pin "8") (pinfunction "8_8") (pintype "passive"))
      (node (ref "U7") (pin "3") (pinfunction "GPIO1_3") (pintype "bidirectional"))
    )
    (net (code "107") (name "U0TXD") (class "Default")
      (node (ref "K1") (pin "10") (pinfunction "10_10") (pintype "passive"))
      (node (ref "U7") (pin "2") (pinfunction "GPIO0_2") (pintype "bidirectional"))
    )
    (net (code "108") (name "USB_D+") (class "Default")
      (node (ref "R8") (pin "2") (pinfunction "2_2") (pintype "passive"))
      (node (ref "U4") (pin "27") (pinfunction "IO19_27") (pintype "bidirectional"))
    )
    (net (code "109") (name "USB_D-") (class "Default")
      (node (ref "R10") (pin "2") (pinfunction "2_2") (pintype "passive"))
      (node (ref "U4") (pin "26") (pinfunction "IO18_26") (pintype "bidirectional"))
    )
    (net (code "110") (name "VBAT") (class "Default")
      (node (ref "C65") (pin "1") (pinfunction "1_1") (pintype "passive"))
      (node (ref "JP6") (pin "2") (pinfunction "2_2") (pintype "passive"))
      (node (ref "Q3") (pin "3") (pinfunction "D_3") (pintype "passive"))
      (node (ref "R13") (pin "2") (pinfunction "2_2") (pintype "passive"))
      (node (ref "U5") (pin "3") (pinfunction "VBAT_3") (pintype "power_in"))
    )
    (net (code "111") (name "VBUS") (class "Default")
      (node (ref "D9") (pin "A") (pinfunction "A_A") (pintype "passive"))
      (node (ref "J3") (pin "VBUS1") (pinfunction "VBUS_VBUS1") (pintype "bidirectional"))
      (node (ref "J3") (pin "VBUS2") (pinfunction "VBUS_VBUS2") (pintype "bidirectional"))
      (node (ref "J5") (pin "VBUS1") (pinfunction "VBUS_VBUS1") (pintype "bidirectional"))
      (node (ref "J5") (pin "VBUS2") (pinfunction "VBUS_VBUS2") (pintype "bidirectional"))
      (node (ref "TP5") (pin "TP") (pinfunction "TP_TP") (pintype "input"))
    )
    (net (code "112") (name "VCM") (class "Default")
      (node (ref "C13") (pin "1") (pinfunction "1_1") (pintype "passive"))
      (node (ref "U$3") (pin "4") (pinfunction "VCM_4") (pintype "bidirectional"))
    )
    (net (code "113") (name "VDD") (class "Default")
      (node (ref "C64") (pin "1") (pinfunction "1_1") (pintype "passive"))
      (node (ref "D10") (pin "A") (pinfunction "A_A") (pintype "passive"))
      (node (ref "D8") (pin "C") (pinfunction "C_C") (pintype "passive"))
      (node (ref "D9") (pin "C") (pinfunction "C_C") (pintype "passive"))
      (node (ref "LED1") (pin "5") (pinfunction "4_5") (pintype "passive"))
      (node (ref "Q3") (pin "1") (pinfunction "G_1") (pintype "passive"))
      (node (ref "R30") (pin "2") (pinfunction "2_2") (pintype "passive"))
      (node (ref "R4") (pin "2") (pinfunction "2_2") (pintype "passive"))
      (node (ref "SWIO7") (pin "TP") (pinfunction "TP_TP") (pintype "input"))
      (node (ref "U5") (pin "4") (pinfunction "VIN_4") (pintype "power_in"))
    )
    (net (code "114") (name "unconnected-(J4-DATA1-Pad8)") (class "Default")
      (node (ref "J4") (pin "8") (pinfunction "DATA1_8") (pintype "bidirectional"))
    )
    (net (code "115") (name "unconnected-(J4-DATA2-Pad1)") (class "Default")
      (node (ref "J4") (pin "1") (pinfunction "DATA2_1") (pintype "bidirectional"))
    )
    (net (code "116") (name "unconnected-(J4-DETECH-Pad9)") (class "Default")
      (node (ref "J4") (pin "9") (pinfunction "DETECH_9") (pintype "passive"))
    )
    (net (code "117") (name "unconnected-(K1-Pad3)") (class "Default")
      (node (ref "K1") (pin "3") (pinfunction "3_3") (pintype "passive"))
    )
    (net (code "118") (name "unconnected-(K1-Pad5)") (class "Default")
      (node (ref "K1") (pin "5") (pinfunction "5_5") (pintype "passive"))
    )
    (net (code "119") (name "unconnected-(K1-Pad7)") (class "Default")
      (node (ref "K1") (pin "7") (pinfunction "7_7") (pintype "passive"))
    )
    (net (code "120") (name "unconnected-(K1-Pad11)") (class "Default")
      (node (ref "K1") (pin "11") (pinfunction "11_11") (pintype "passive"))
    )
    (net (code "121") (name "unconnected-(K1-Pad13)") (class "Default")
      (node (ref "K1") (pin "13") (pinfunction "13_13") (pintype "passive"))
    )
    (net (code "122") (name "unconnected-(K1-Pad15)") (class "Default")
      (node (ref "K1") (pin "15") (pinfunction "15_15") (pintype "passive"))
    )
    (net (code "123") (name "unconnected-(K1-Pad18)") (class "Default")
      (node (ref "K1") (pin "18") (pinfunction "18_18") (pintype "passive"))
    )
    (net (code "124") (name "unconnected-(K1-Pad27)") (class "Default")
      (node (ref "K1") (pin "27") (pinfunction "27_27") (pintype "passive"))
    )
    (net (code "125") (name "unconnected-(K1-Pad28)") (class "Default")
      (node (ref "K1") (pin "28") (pinfunction "28_28") (pintype "passive"))
    )
    (net (code "126") (name "unconnected-(K1-Pad32)") (class "Default")
      (node (ref "K1") (pin "32") (pinfunction "32_32") (pintype "passive"))
    )
    (net (code "127") (name "unconnected-(K1-Pad33)") (class "Default")
      (node (ref "K1") (pin "33") (pinfunction "33_33") (pintype "passive"))
    )
    (net (code "128") (name "unconnected-(K1-Pad35)") (class "Default")
      (node (ref "K1") (pin "35") (pinfunction "35_35") (pintype "passive"))
    )
    (net (code "129") (name "unconnected-(K1-Pad37)") (class "Default")
      (node (ref "K1") (pin "37") (pinfunction "37_37") (pintype "passive"))
    )
    (net (code "130") (name "unconnected-(K1-Pad38)") (class "Default")
      (node (ref "K1") (pin "38") (pinfunction "38_38") (pintype "passive"))
    )
    (net (code "131") (name "unconnected-(K1-Pad40)") (class "Default")
      (node (ref "K1") (pin "40") (pinfunction "40_40") (pintype "passive"))
    )
    (net (code "132") (name "unconnected-(S2-5-Pad4)") (class "Default")
      (node (ref "S2") (pin "4") (pinfunction "5_4") (pintype "bidirectional"))
    )
    (net (code "133") (name "unconnected-(S2-6_-_C-Pad5)") (class "Default")
      (node (ref "S2") (pin "5") (pinfunction "6_-_C_5") (pintype "bidirectional"))
    )
    (net (code "134") (name "unconnected-(S2-7-Pad6)") (class "Default")
      (node (ref "S2") (pin "6") (pinfunction "7_6") (pintype "bidirectional"))
    )
    (net (code "135") (name "unconnected-(SW1-P-PadA)") (class "Default")
      (node (ref "SW1") (pin "A") (pinfunction "P_A") (pintype "passive"))
    )
    (net (code "136") (name "unconnected-(SW1-S-PadB)") (class "Default")
      (node (ref "SW1") (pin "B") (pinfunction "S_B") (pintype "passive"))
    )
    (net (code "137") (name "unconnected-(SW2-P-PadA)") (class "Default")
      (node (ref "SW2") (pin "A") (pinfunction "P_A") (pintype "passive"))
    )
    (net (code "138") (name "unconnected-(SW2-S-PadB)") (class "Default")
      (node (ref "SW2") (pin "B") (pinfunction "S_B") (pintype "passive"))
    )
    (net (code "139") (name "unconnected-(SW4-P-PadA)") (class "Default")
      (node (ref "SW4") (pin "A") (pinfunction "P_A") (pintype "passive"))
    )
    (net (code "140") (name "unconnected-(SW4-S-PadB)") (class "Default")
      (node (ref "SW4") (pin "B") (pinfunction "S_B") (pintype "passive"))
    )
    (net (code "141") (name "unconnected-(SW5-P-PadA)") (class "Default")
      (node (ref "SW5") (pin "A") (pinfunction "P_A") (pintype "passive"))
    )
    (net (code "142") (name "unconnected-(SW5-S-PadB)") (class "Default")
      (node (ref "SW5") (pin "B") (pinfunction "S_B") (pintype "passive"))
    )
    (net (code "143") (name "unconnected-(U$3-DIAG_END-Pad21)") (class "Default")
      (node (ref "U$3") (pin "21") (pinfunction "DIAG_END_21") (pintype "bidirectional"))
    )
    (net (code "144") (name "unconnected-(U$3-DNC-Pad5)") (class "Default")
      (node (ref "U$3") (pin "5") (pinfunction "DNC_5") (pintype "bidirectional"))
    )
    (net (code "145") (name "unconnected-(U$3-DNC-Pad6)") (class "Default")
      (node (ref "U$3") (pin "6") (pinfunction "DNC_6") (pintype "bidirectional"))
    )
    (net (code "146") (name "unconnected-(U$3-DNC-Pad10)") (class "Default")
      (node (ref "U$3") (pin "10") (pinfunction "DNC_10") (pintype "bidirectional"))
    )
    (net (code "147") (name "unconnected-(U$3-DNC-Pad34)") (class "Default")
      (node (ref "U$3") (pin "34") (pinfunction "DNC_34") (pintype "bidirectional"))
    )
    (net (code "148") (name "unconnected-(U$3-DNC-Pad35)") (class "Default")
      (node (ref "U$3") (pin "35") (pinfunction "DNC_35") (pintype "bidirectional"))
    )
    (net (code "149") (name "unconnected-(U$3-LED_ALM-Pad22)") (class "Default")
      (node (ref "U$3") (pin "22") (pinfunction "LED_ALM_22") (pintype "bidirectional"))
    )
    (net (code "150") (name "unconnected-(U$3-PD_ALM-Pad23)") (class "Default")
      (node (ref "U$3") (pin "23") (pinfunction "PD_ALM_23") (pintype "bidirectional"))
    )
    (net (code "151") (name "unconnected-(U$3-RSVD-Pad9)") (class "Default")
      (node (ref "U$3") (pin "9") (pinfunction "RSVD_9") (pintype "bidirectional"))
    )
    (net (code "152") (name "unconnected-(U$26-NC-Pad4)") (class "Default")
      (node (ref "U$26") (pin "4") (pinfunction "NC_4") (pintype "bidirectional"))
    )
    (net (code "153") (name "unconnected-(U$30-AOUT-PadC2)") (class "Default")
      (node (ref "U$30") (pin "C2") (pinfunction "AOUT_C2") (pintype "bidirectional"))
    )
    (net (code "154") (name "unconnected-(U$31-NC-Pad1)") (class "Default")
      (node (ref "U$31") (pin "1") (pinfunction "NC_1") (pintype "bidirectional"))
    )
    (net (code "155") (name "unconnected-(U3-BP-Pad4)") (class "Default")
      (node (ref "U3") (pin "4") (pinfunction "BP_4") (pintype "input"))
    )
    (net (code "156") (name "unconnected-(U4-NC-Pad4)") (class "Default")
      (node (ref "U4") (pin "4") (pinfunction "NC_4") (pintype "no_connect"))
    )
    (net (code "157") (name "unconnected-(U4-NC-Pad7)") (class "Default")
      (node (ref "U4") (pin "7") (pinfunction "NC_7") (pintype "no_connect"))
    )
    (net (code "158") (name "unconnected-(U4-NC-Pad9)") (class "Default")
      (node (ref "U4") (pin "9") (pinfunction "NC_9") (pintype "no_connect"))
    )
    (net (code "159") (name "unconnected-(U4-NC-Pad10)") (class "Default")
      (node (ref "U4") (pin "10") (pinfunction "NC_10") (pintype "no_connect"))
    )
    (net (code "160") (name "unconnected-(U4-NC-Pad15)") (class "Default")
      (node (ref "U4") (pin "15") (pinfunction "NC_15") (pintype "no_connect"))
    )
    (net (code "161") (name "unconnected-(U4-NC-Pad17)") (class "Default")
      (node (ref "U4") (pin "17") (pinfunction "NC_17") (pintype "no_connect"))
    )
    (net (code "162") (name "unconnected-(U4-NC-Pad24)") (class "Default")
      (node (ref "U4") (pin "24") (pinfunction "NC_24") (pintype "no_connect"))
    )
    (net (code "163") (name "unconnected-(U4-NC-Pad25)") (class "Default")
      (node (ref "U4") (pin "25") (pinfunction "NC_25") (pintype "no_connect"))
    )
    (net (code "164") (name "unconnected-(U4-NC-Pad28)") (class "Default")
      (node (ref "U4") (pin "28") (pinfunction "NC_28") (pintype "no_connect"))
    )
    (net (code "165") (name "unconnected-(U4-NC-Pad29)") (class "Default")
      (node (ref "U4") (pin "29") (pinfunction "NC_29") (pintype "no_connect"))
    )
    (net (code "166") (name "unconnected-(U4-NC-Pad32)") (class "Default")
      (node (ref "U4") (pin "32") (pinfunction "NC_32") (pintype "no_connect"))
    )
    (net (code "167") (name "unconnected-(U4-NC-Pad33)") (class "Default")
      (node (ref "U4") (pin "33") (pinfunction "NC_33") (pintype "no_connect"))
    )
    (net (code "168") (name "unconnected-(U4-NC-Pad34)") (class "Default")
      (node (ref "U4") (pin "34") (pinfunction "NC_34") (pintype "no_connect"))
    )
    (net (code "169") (name "unconnected-(U4-NC-Pad35)") (class "Default")
      (node (ref "U4") (pin "35") (pinfunction "NC_35") (pintype "no_connect"))
    )
    (net (code "170") (name "unconnected-(X1-Pad1)") (class "Default")
      (node (ref "X1") (pin "1") (pinfunction "1_1") (pintype "passive"))
    )
    (net (code "171") (name "unconnected-(X1-Pad4)") (class "Default")
      (node (ref "X1") (pin "4") (pinfunction "4_4") (pintype "passive"))
    )
    (net (code "172") (name "unconnected-(X1-Pad6)") (class "Default")
      (node (ref "X1") (pin "6") (pinfunction "6_6") (pintype "passive"))
    )
    (net (code "173") (name "unconnected-(X1-Pad8)") (class "Default")
      (node (ref "X1") (pin "8") (pinfunction "8_8") (pintype "passive"))
    )
    (net (code "174") (name "~{ADC_RESET}") (class "Default")
      (node (ref "R47") (pin "2") (pinfunction "2_2") (pintype "passive"))
      (node (ref "U$3") (pin "29") (pinfunction "~{RESET}_29") (pintype "bidirectional"))
    )
    (net (code "175") (name "~{RESET}") (class "Default")
      (node (ref "SW5") (pin "B'") (pinfunction "S1_B'") (pintype "passive"))
      (node (ref "U7") (pin "26") (pinfunction "RUN_26") (pintype "bidirectional"))
    )
  )
)
